# Power_Ctrl_Board_SCH.net
KiCad netlist of a schematic drawn in Altium Designer
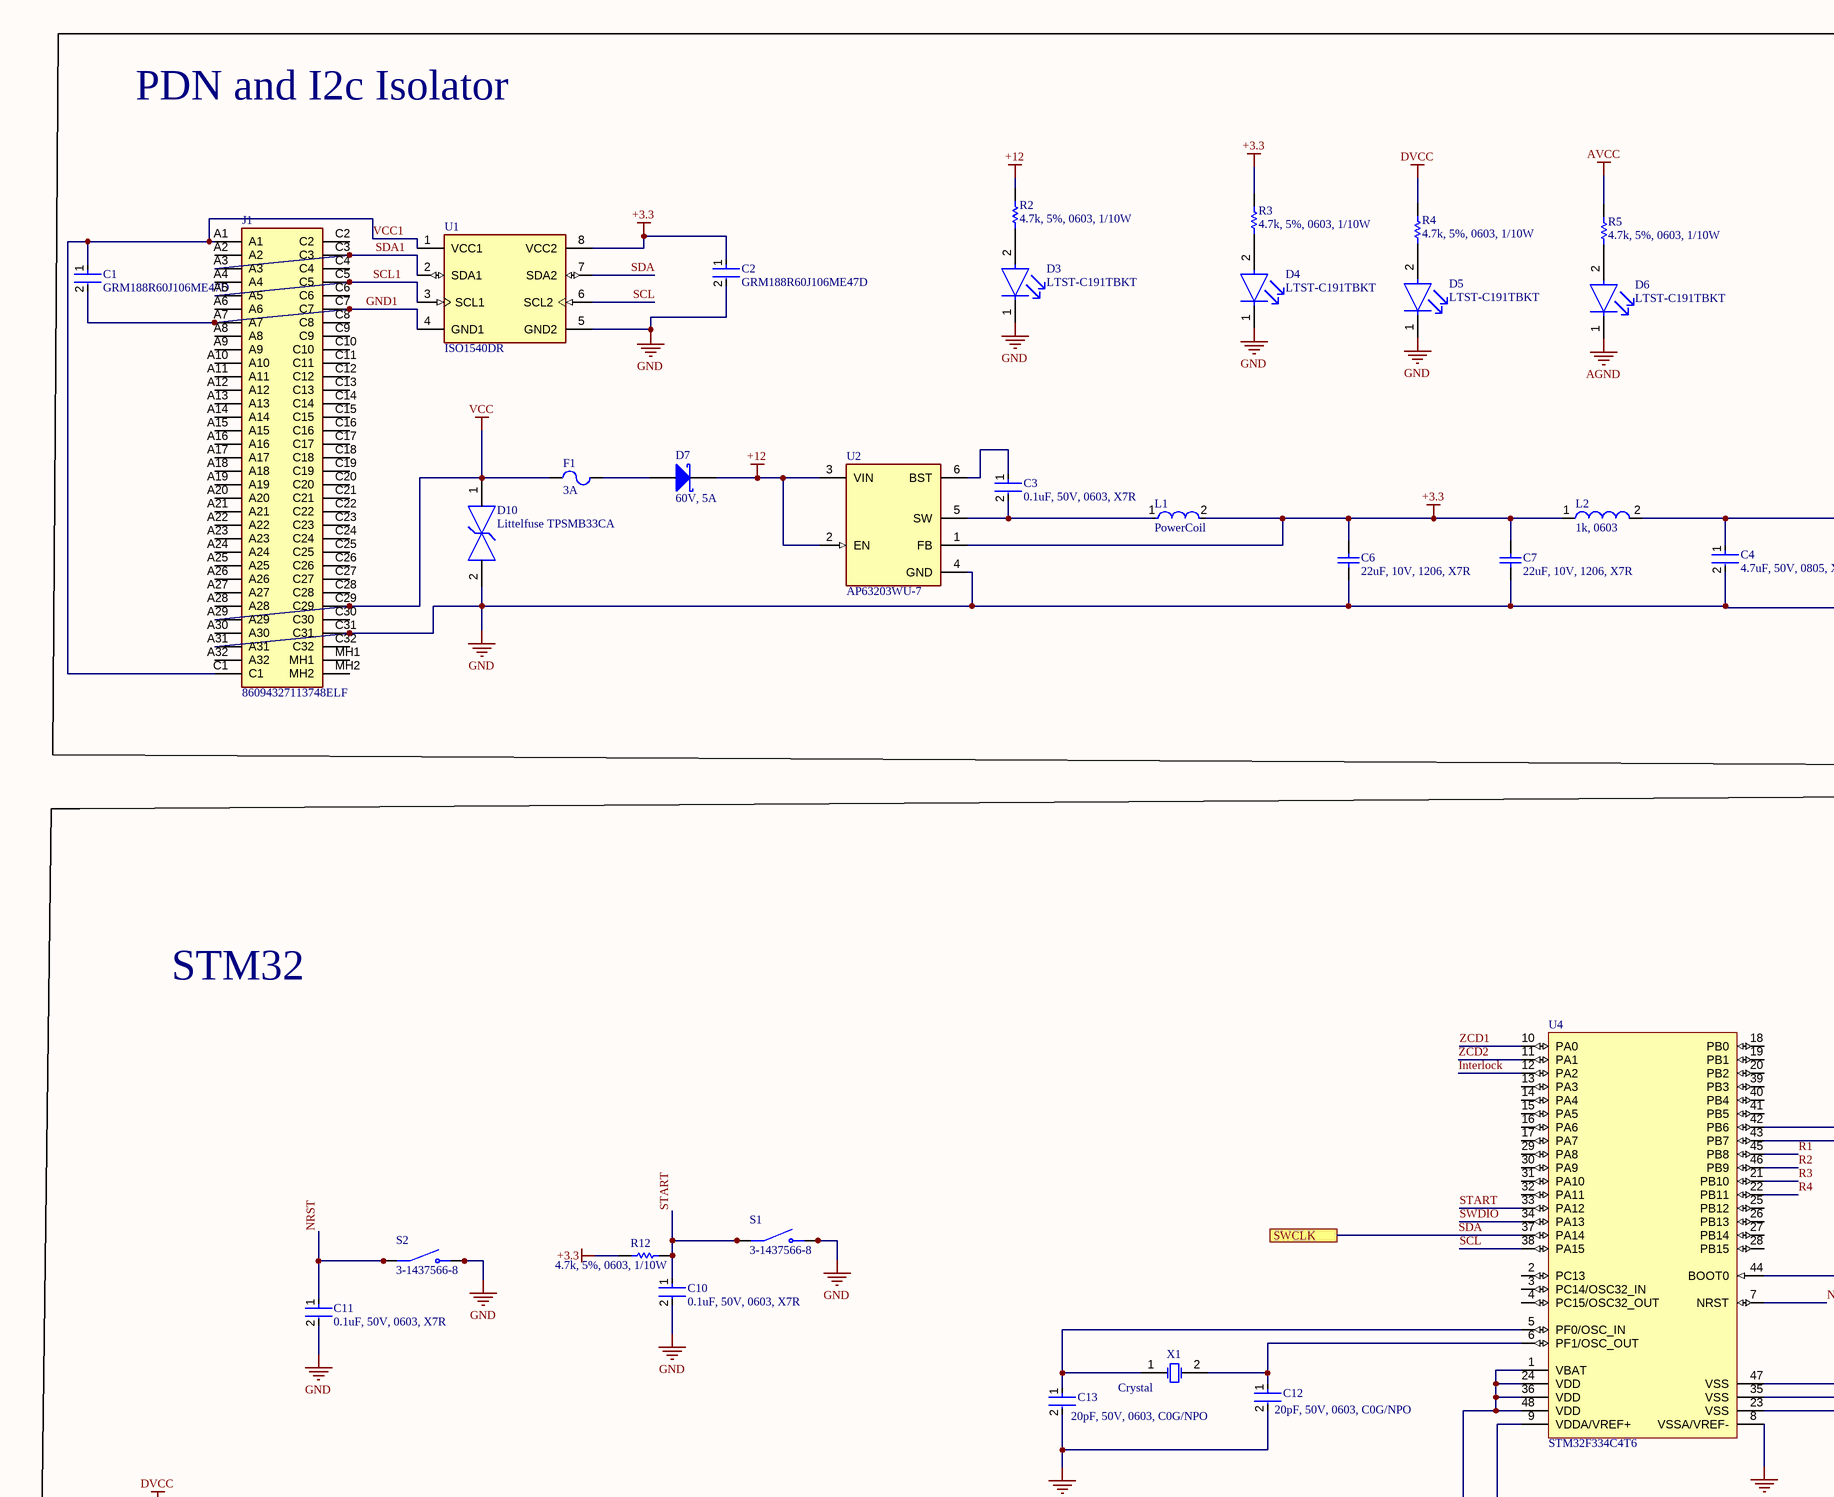
[diagram p0: Power_Ctrl_Board_SCH.SchDoc, top left]
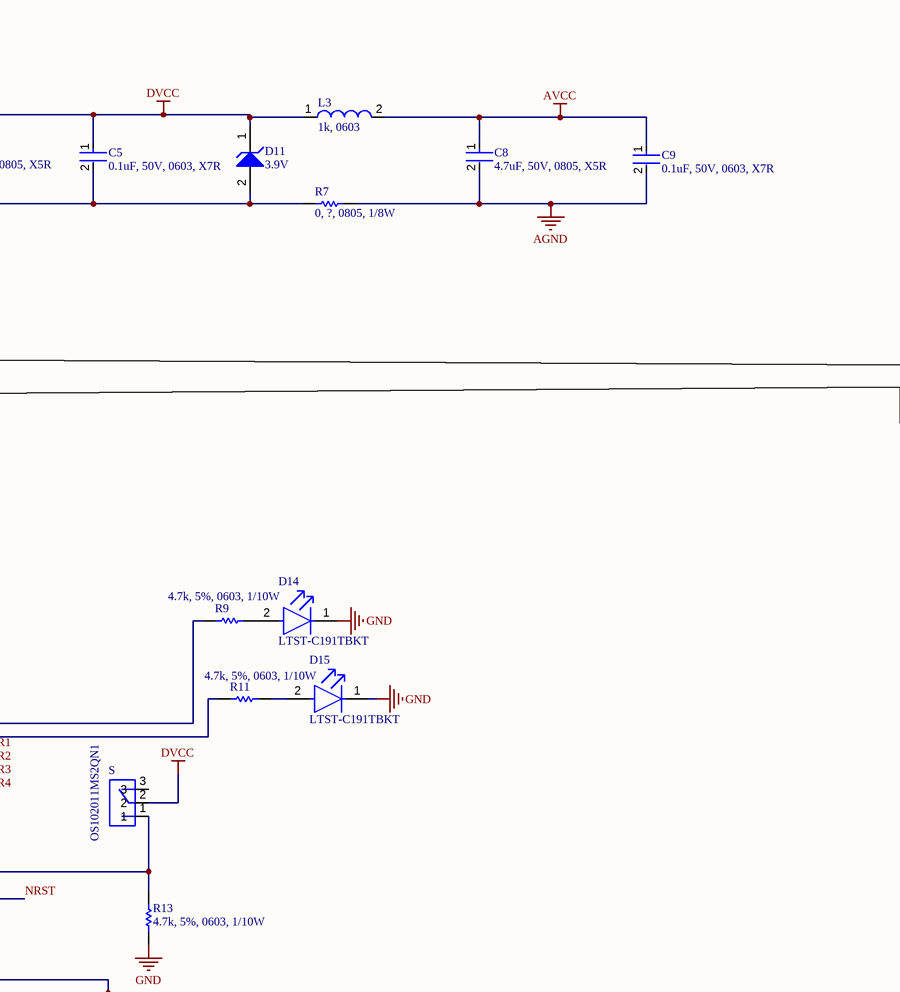
[diagram p1: Power_Ctrl_Board_SCH.SchDoc, top middle]
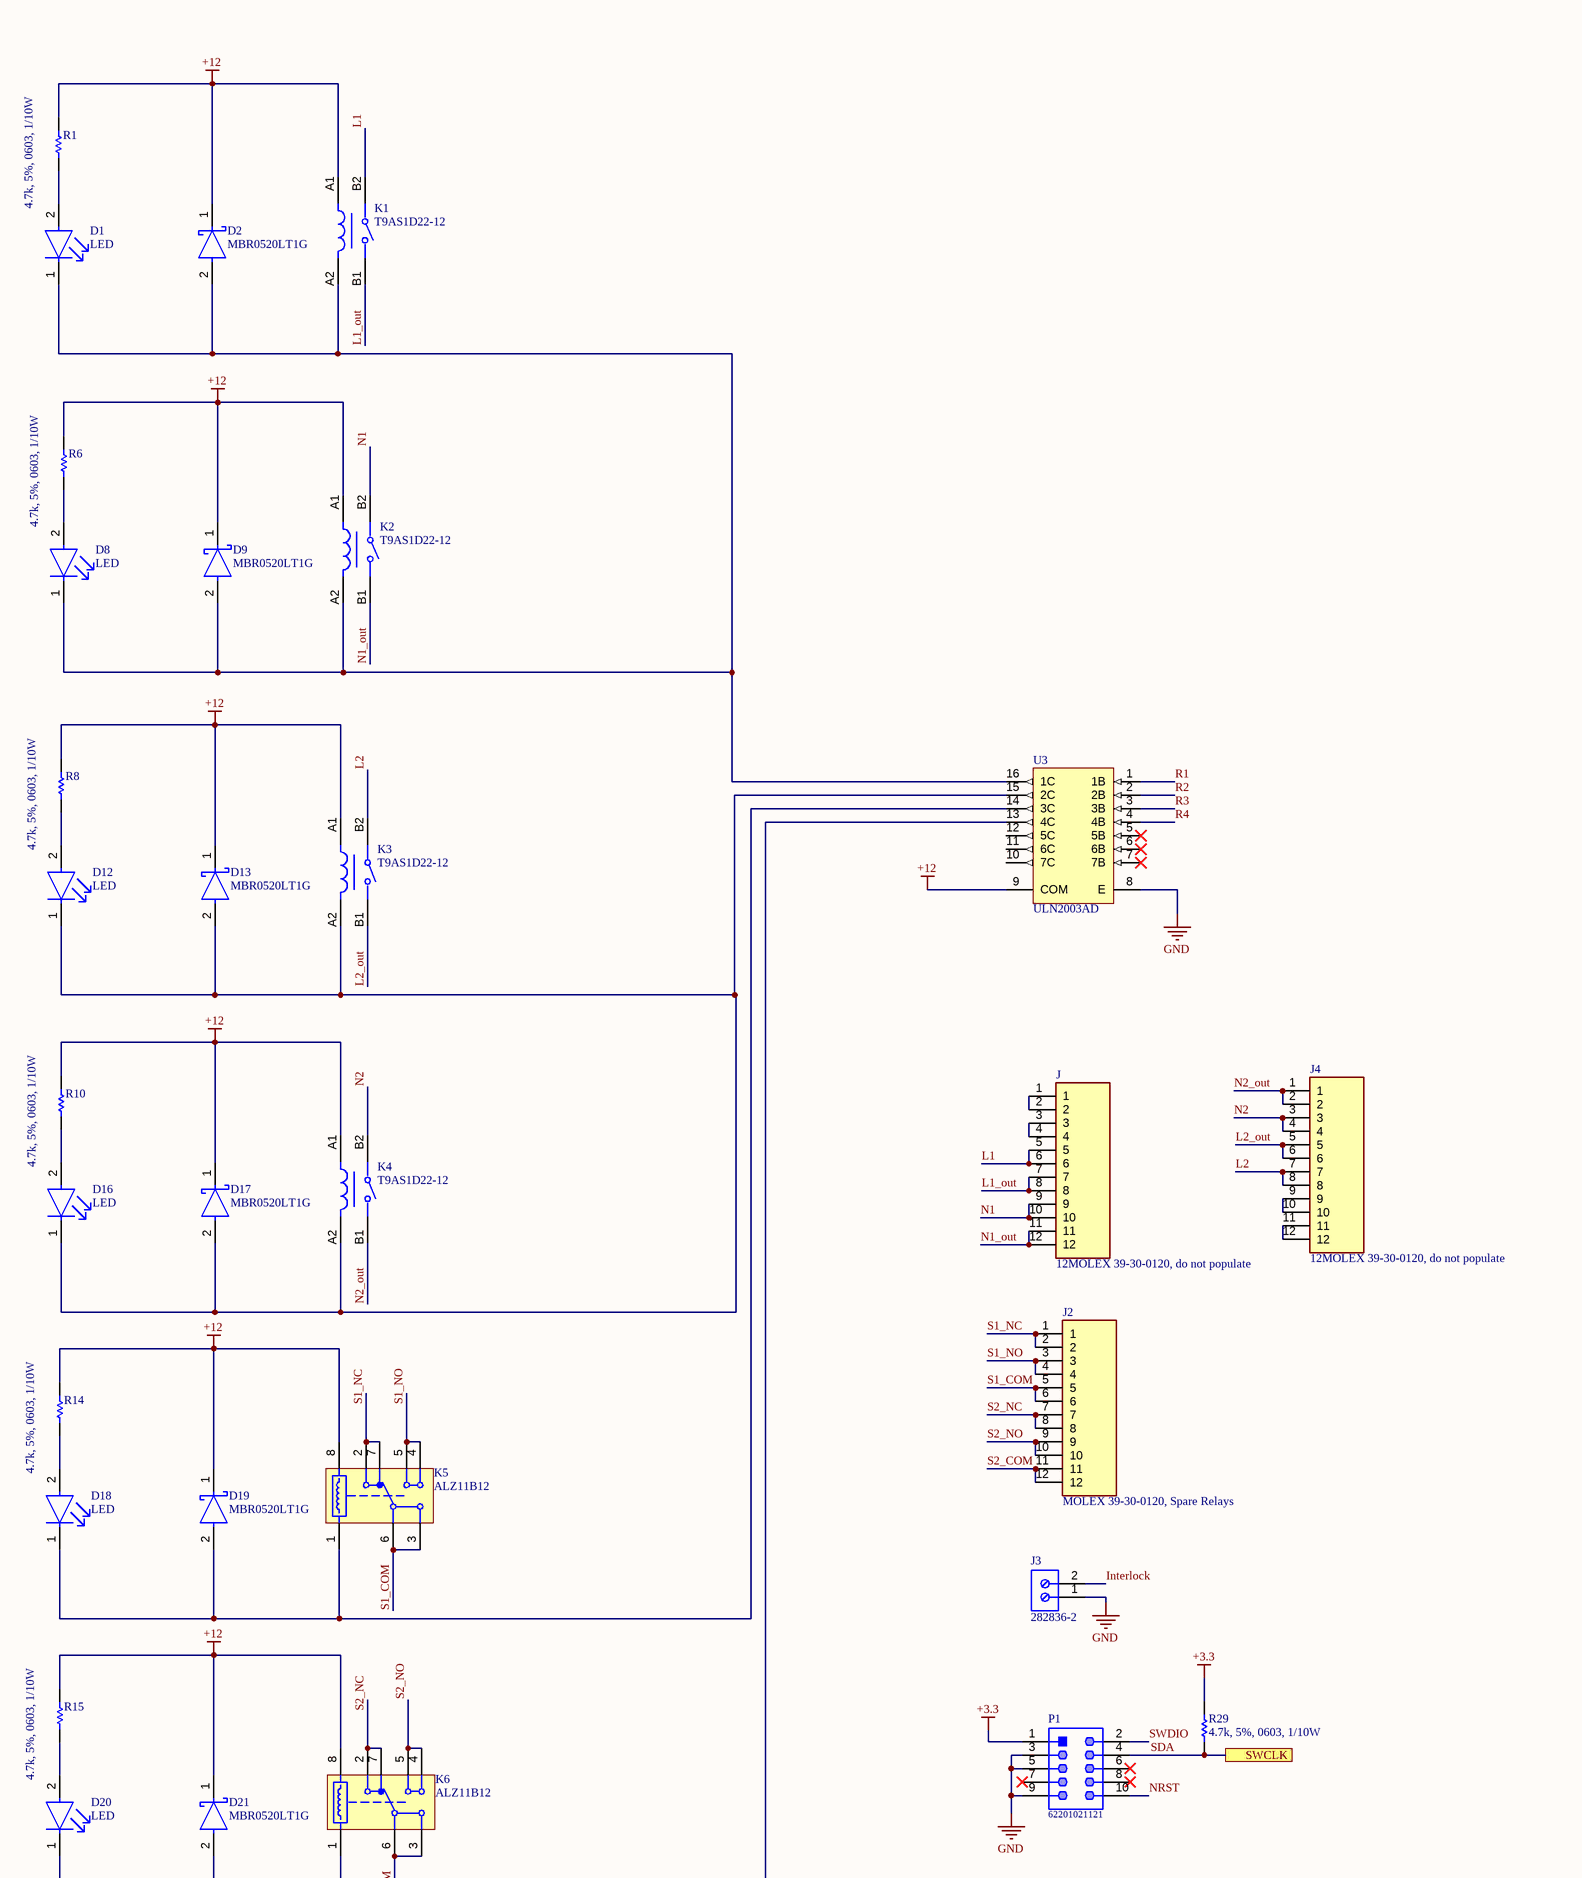
[diagram p2: Power_Ctrl_Board_SCH.SchDoc, top right]
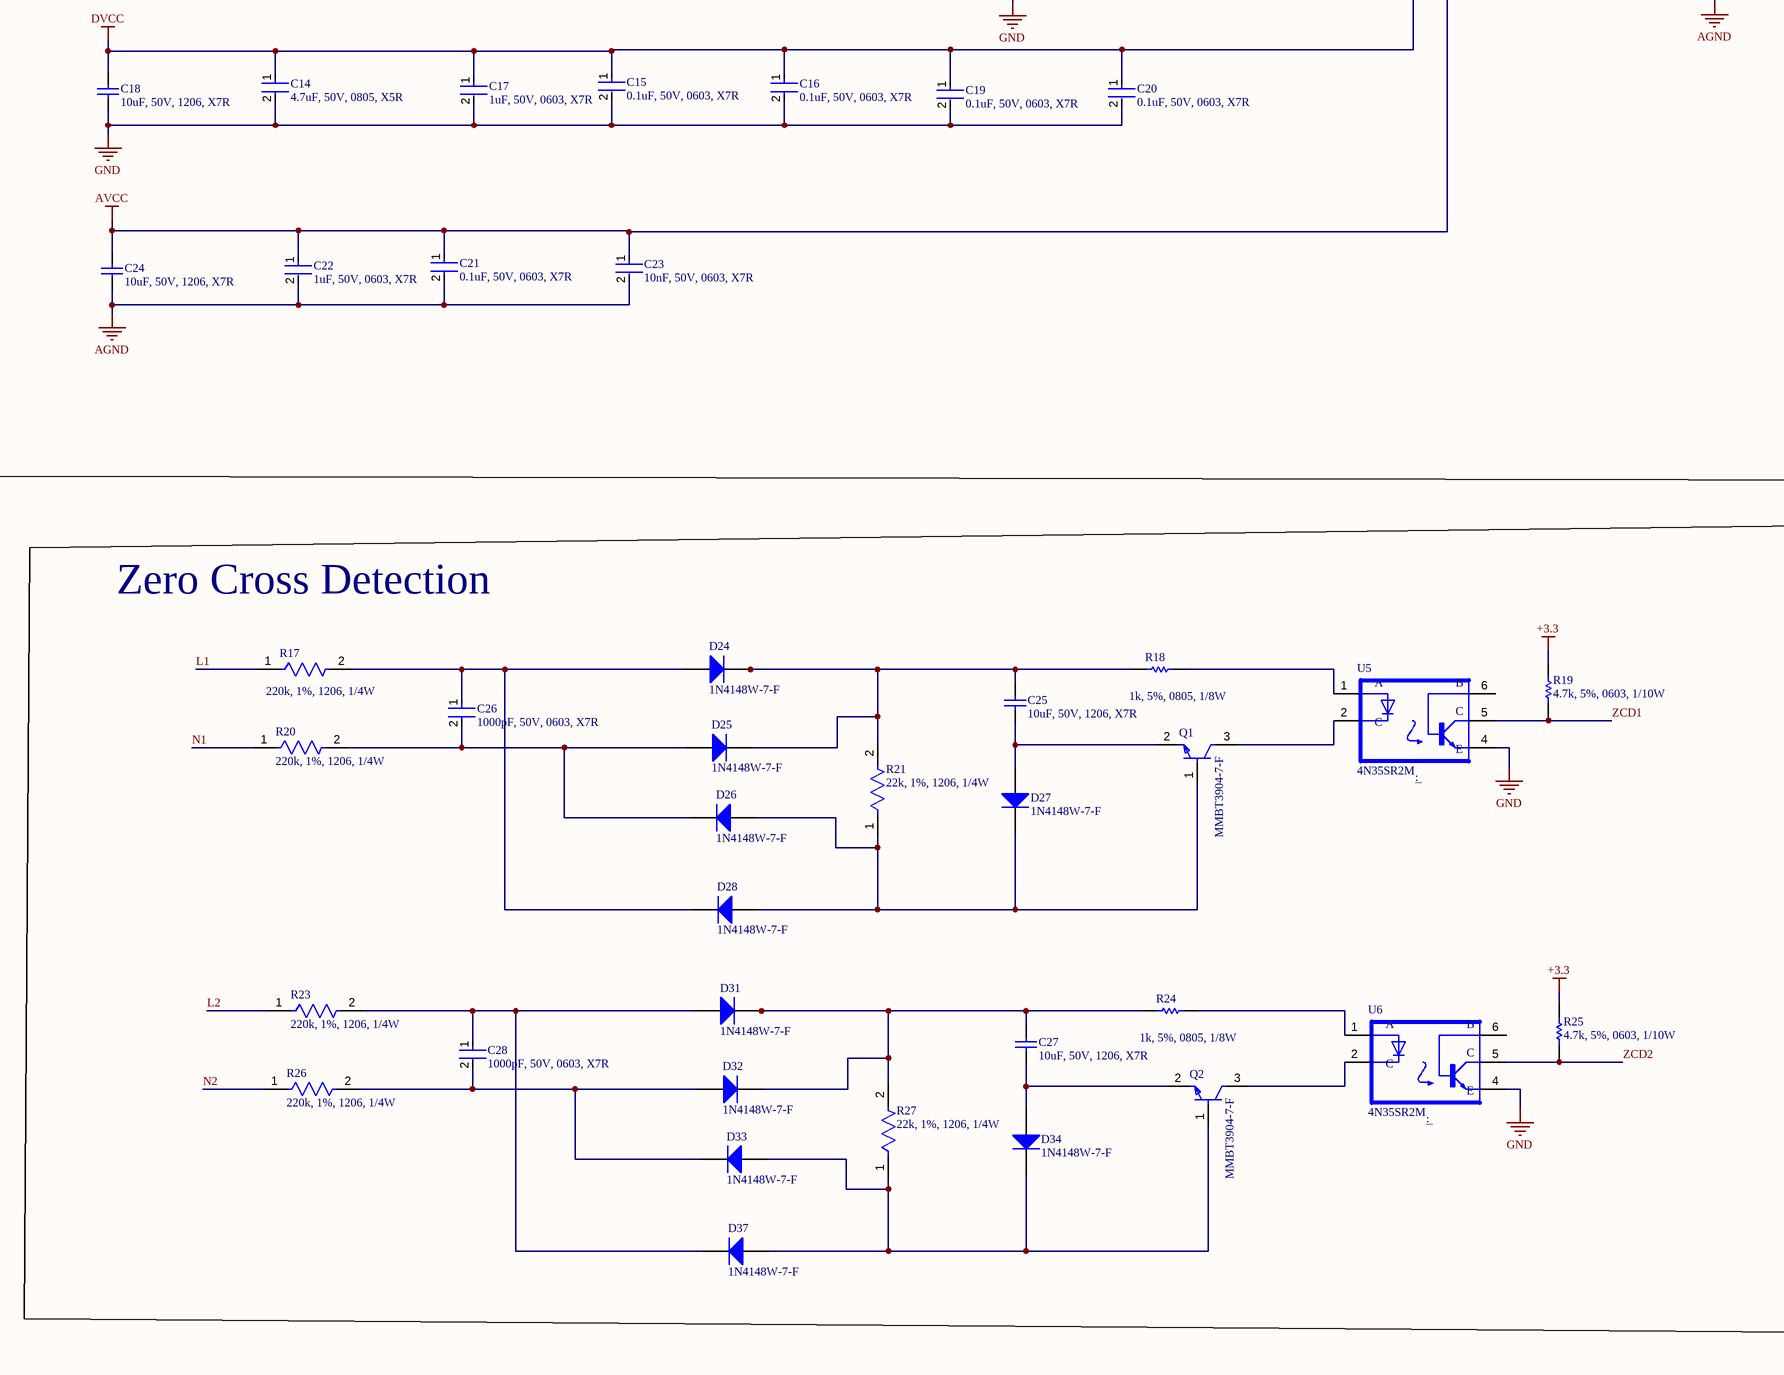
[diagram p3: Power_Ctrl_Board_SCH.SchDoc, bottom left]
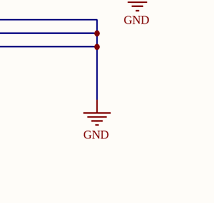
[diagram p4: Power_Ctrl_Board_SCH.SchDoc, bottom middle]
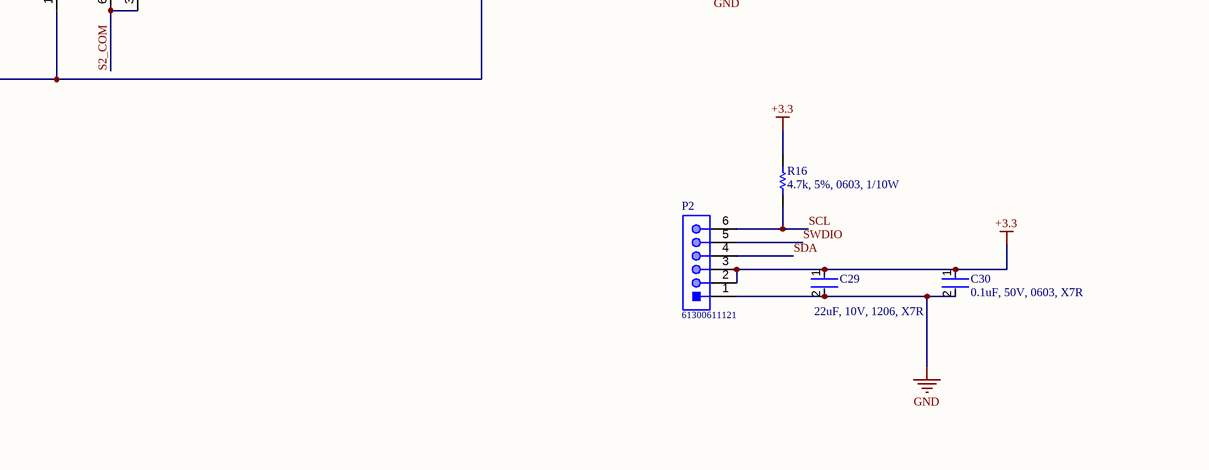
[diagram p5: Power_Ctrl_Board_SCH.SchDoc, bottom right]

(export (version "E")
  (design (tool "Eeschema 10.0.6"))
  (components
    (comp (ref "C1")
      (value "GRM188R60J106ME47D")
      (footprint "FP-GRM188-0_1-e0_2_0_55-IPC_A")
      (description "Chip Multilayer Ceramic Capacitors for General Purpose, 0603, 10uF, X5R, 15%, 20%, 6.3V")
      (fields (field (name "VOLTAGE") "6.3V") (field (name "TOLERANCE") "20%"))
      (libsource (lib "Altium Content Vault") (part "02cd4be3c70576c341d710602a673aa"))
    )
    (comp (ref "C2")
      (value "GRM188R60J106ME47D")
      (footprint "FP-GRM188-0_1-e0_2_0_55-IPC_A")
      (description "Chip Multilayer Ceramic Capacitors for General Purpose, 0603, 10uF, X5R, 15%, 20%, 6.3V")
      (fields (field (name "VOLTAGE") "6.3V") (field (name "TOLERANCE") "20%"))
      (libsource (lib "Altium Content Vault") (part "02cd4be3c70576c341d710602a673aa"))
    )
    (comp (ref "C3")
      (value "0.1uF, 50V, 0603, X7R")
      (footprint "FP-GRM188-0_1-e0_2_0_55-IPC_A")
      (description "Chip Multilayer Ceramic Capacitors for General Purpose, 0603, 10uF, X5R, 15%, 20%, 6.3V")
      (fields (field (name "VOLTAGE") "6.3V") (field (name "TOLERANCE") "20%"))
      (libsource (lib "Altium Content Vault") (part "02cd4be3c70576c341d710602a673aa"))
    )
    (comp (ref "C4")
      (value "4.7uF, 50V, 0805, X5R")
      (footprint "FP-C0805C-DG-MFG")
      (description "CAP CER 10UF 10V X5R 0805")
      (fields (field (name "TOLERANCE") "10%") (field (name "MANUFACTURER PART NUMBER") "C0805C106K8PACTU"))
      (libsource (lib "Altium Content Vault") (part "11868f565c42a9108669ba33697ecf6"))
    )
    (comp (ref "C5")
      (value "0.1uF, 50V, 0603, X7R")
      (footprint "FP-GRM188-0_1-e0_2_0_55-IPC_A")
      (description "Chip Multilayer Ceramic Capacitors for General Purpose, 0603, 10uF, X5R, 15%, 20%, 6.3V")
      (fields (field (name "VOLTAGE") "6.3V") (field (name "TOLERANCE") "20%"))
      (libsource (lib "Altium Content Vault") (part "02cd4be3c70576c341d710602a673aa"))
    )
    (comp (ref "C6")
      (value "22uF, 10V, 1206, X7R")
      (footprint "AVX-1206-2_L")
      (description "Chip Capacitor, 1 nF, +/- 10%, -55 to 125 degC, 1206 (3216 Metric), RoHS, Tape and Reel")
      (fields (field (name "TOLERANCE") "10%") (field (name "PARTNUMBER") "1206GC102KAT1A"))
      (libsource (lib "Altium Content Vault") (part "CAP-NP-2"))
    )
    (comp (ref "C7")
      (value "22uF, 10V, 1206, X7R")
      (footprint "AVX-1206-2_L")
      (description "Chip Capacitor, 1 nF, +/- 10%, -55 to 125 degC, 1206 (3216 Metric), RoHS, Tape and Reel")
      (fields (field (name "TOLERANCE") "10%") (field (name "PARTNUMBER") "1206GC102KAT1A"))
      (libsource (lib "Altium Content Vault") (part "CAP-NP-2"))
    )
    (comp (ref "C8")
      (value "4.7uF, 50V, 0805, X5R")
      (footprint "FP-C0805C-DG-MFG")
      (description "CAP CER 10UF 10V X5R 0805")
      (fields (field (name "TOLERANCE") "10%") (field (name "MANUFACTURER PART NUMBER") "C0805C106K8PACTU"))
      (libsource (lib "Altium Content Vault") (part "11868f565c42a9108669ba33697ecf6"))
    )
    (comp (ref "C9")
      (value "0.1uF, 50V, 0603, X7R")
      (footprint "FP-GRM188-0_1-e0_2_0_55-IPC_A")
      (description "Chip Multilayer Ceramic Capacitors for General Purpose, 0603, 10uF, X5R, 15%, 20%, 6.3V")
      (fields (field (name "VOLTAGE") "6.3V") (field (name "TOLERANCE") "20%"))
      (libsource (lib "Altium Content Vault") (part "02cd4be3c70576c341d710602a673aa"))
    )
    (comp (ref "C10")
      (value "0.1uF, 50V, 0603, X7R")
      (footprint "FP-GRM188-0_1-e0_2_0_55-IPC_A")
      (description "Chip Multilayer Ceramic Capacitors for General Purpose, 0603, 10uF, X5R, 15%, 20%, 6.3V")
      (fields (field (name "VOLTAGE") "6.3V") (field (name "TOLERANCE") "20%"))
      (libsource (lib "Altium Content Vault") (part "02cd4be3c70576c341d710602a673aa"))
    )
    (comp (ref "C11")
      (value "0.1uF, 50V, 0603, X7R")
      (footprint "FP-GRM188-0_1-e0_2_0_55-IPC_A")
      (description "Chip Multilayer Ceramic Capacitors for General Purpose, 0603, 10uF, X5R, 15%, 20%, 6.3V")
      (fields (field (name "VOLTAGE") "6.3V") (field (name "TOLERANCE") "20%"))
      (libsource (lib "Altium Content Vault") (part "02cd4be3c70576c341d710602a673aa"))
    )
    (comp (ref "C12")
      (value "20pF, 50V, 0603, C0G/NPO")
      (footprint "FP-GRM188-0_1-e0_2_0_55-IPC_A")
      (description "Chip Multilayer Ceramic Capacitors for General Purpose, 0603, 10uF, X5R, 15%, 20%, 6.3V")
      (fields (field (name "VOLTAGE") "6.3V") (field (name "TOLERANCE") "20%"))
      (libsource (lib "Altium Content Vault") (part "02cd4be3c70576c341d710602a673aa"))
    )
    (comp (ref "C13")
      (value "20pF, 50V, 0603, C0G/NPO")
      (footprint "FP-GRM188-0_1-e0_2_0_55-IPC_A")
      (description "Chip Multilayer Ceramic Capacitors for General Purpose, 0603, 10uF, X5R, 15%, 20%, 6.3V")
      (fields (field (name "VOLTAGE") "6.3V") (field (name "TOLERANCE") "20%"))
      (libsource (lib "Altium Content Vault") (part "02cd4be3c70576c341d710602a673aa"))
    )
    (comp (ref "C14")
      (value "4.7uF, 50V, 0805, X5R")
      (footprint "FP-C0805C-DG-MFG")
      (description "CAP CER 10UF 10V X5R 0805")
      (fields (field (name "TOLERANCE") "10%") (field (name "MANUFACTURER PART NUMBER") "C0805C106K8PACTU"))
      (libsource (lib "Altium Content Vault") (part "11868f565c42a9108669ba33697ecf6"))
    )
    (comp (ref "C15")
      (value "0.1uF, 50V, 0603, X7R")
      (footprint "FP-GRM188-0_1-e0_2_0_55-IPC_A")
      (description "Chip Multilayer Ceramic Capacitors for General Purpose, 0603, 10uF, X5R, 15%, 20%, 6.3V")
      (fields (field (name "VOLTAGE") "6.3V") (field (name "TOLERANCE") "20%"))
      (libsource (lib "Altium Content Vault") (part "02cd4be3c70576c341d710602a673aa"))
    )
    (comp (ref "C16")
      (value "0.1uF, 50V, 0603, X7R")
      (footprint "FP-GRM188-0_1-e0_2_0_55-IPC_A")
      (description "Chip Multilayer Ceramic Capacitors for General Purpose, 0603, 10uF, X5R, 15%, 20%, 6.3V")
      (fields (field (name "VOLTAGE") "6.3V") (field (name "TOLERANCE") "20%"))
      (libsource (lib "Altium Content Vault") (part "02cd4be3c70576c341d710602a673aa"))
    )
    (comp (ref "C17")
      (value "1uF, 50V, 0603, X7R")
      (footprint "FP-GRM188-0_1-e0_2_0_55-IPC_A")
      (description "Chip Multilayer Ceramic Capacitors for General Purpose, 0603, 10uF, X5R, 15%, 20%, 6.3V")
      (fields (field (name "VOLTAGE") "6.3V") (field (name "TOLERANCE") "20%"))
      (libsource (lib "Altium Content Vault") (part "02cd4be3c70576c341d710602a673aa"))
    )
    (comp (ref "C18")
      (value "10uF, 50V, 1206, X7R")
      (footprint "AVX-1206-2_L")
      (description "Chip Capacitor, 1 nF, +/- 10%, -55 to 125 degC, 1206 (3216 Metric), RoHS, Tape and Reel")
      (fields (field (name "TOLERANCE") "10%") (field (name "PARTNUMBER") "1206GC102KAT1A"))
      (libsource (lib "Altium Content Vault") (part "CAP-NP-2"))
    )
    (comp (ref "C19")
      (value "0.1uF, 50V, 0603, X7R")
      (footprint "FP-GRM188-0_1-e0_2_0_55-IPC_A")
      (description "Chip Multilayer Ceramic Capacitors for General Purpose, 0603, 10uF, X5R, 15%, 20%, 6.3V")
      (fields (field (name "VOLTAGE") "6.3V") (field (name "TOLERANCE") "20%"))
      (libsource (lib "Altium Content Vault") (part "02cd4be3c70576c341d710602a673aa"))
    )
    (comp (ref "C20")
      (value "0.1uF, 50V, 0603, X7R")
      (footprint "FP-GRM188-0_1-e0_2_0_55-IPC_A")
      (description "Chip Multilayer Ceramic Capacitors for General Purpose, 0603, 10uF, X5R, 15%, 20%, 6.3V")
      (fields (field (name "VOLTAGE") "6.3V") (field (name "TOLERANCE") "20%"))
      (libsource (lib "Altium Content Vault") (part "02cd4be3c70576c341d710602a673aa"))
    )
    (comp (ref "C21")
      (value "0.1uF, 50V, 0603, X7R")
      (footprint "FP-GRM188-0_1-e0_2_0_55-IPC_A")
      (description "Chip Multilayer Ceramic Capacitors for General Purpose, 0603, 10uF, X5R, 15%, 20%, 6.3V")
      (fields (field (name "VOLTAGE") "6.3V") (field (name "TOLERANCE") "20%"))
      (libsource (lib "Altium Content Vault") (part "02cd4be3c70576c341d710602a673aa"))
    )
    (comp (ref "C22")
      (value "1uF, 50V, 0603, X7R")
      (footprint "FP-GRM188-0_1-e0_2_0_55-IPC_A")
      (description "Chip Multilayer Ceramic Capacitors for General Purpose, 0603, 10uF, X5R, 15%, 20%, 6.3V")
      (fields (field (name "VOLTAGE") "6.3V") (field (name "TOLERANCE") "20%"))
      (libsource (lib "Altium Content Vault") (part "02cd4be3c70576c341d710602a673aa"))
    )
    (comp (ref "C23")
      (value "10nF, 50V, 0603, X7R")
      (footprint "FP-GRM188-0_1-e0_2_0_55-IPC_A")
      (description "Chip Multilayer Ceramic Capacitors for General Purpose, 0603, 10uF, X5R, 15%, 20%, 6.3V")
      (fields (field (name "VOLTAGE") "6.3V") (field (name "TOLERANCE") "20%"))
      (libsource (lib "Altium Content Vault") (part "02cd4be3c70576c341d710602a673aa"))
    )
    (comp (ref "C24")
      (value "10uF, 50V, 1206, X7R")
      (footprint "AVX-1206-2_L")
      (description "Chip Capacitor, 1 nF, +/- 10%, -55 to 125 degC, 1206 (3216 Metric), RoHS, Tape and Reel")
      (fields (field (name "TOLERANCE") "10%") (field (name "PARTNUMBER") "1206GC102KAT1A"))
      (libsource (lib "Altium Content Vault") (part "CAP-NP-2"))
    )
    (comp (ref "C25")
      (value "10uF, 50V, 1206, X7R")
      (footprint "AVX-1206-2_L")
      (description "Chip Capacitor, 1 nF, +/- 10%, -55 to 125 degC, 1206 (3216 Metric), RoHS, Tape and Reel")
      (fields (field (name "TOLERANCE") "10%") (field (name "PARTNUMBER") "1206GC102KAT1A"))
      (libsource (lib "Altium Content Vault") (part "CAP-NP-2"))
    )
    (comp (ref "C26")
      (value "1000pF, 50V, 0603, X7R")
      (footprint "FP-GRM188-0_1-e0_2_0_55-IPC_A")
      (description "Chip Multilayer Ceramic Capacitors for General Purpose, 0603, 10uF, X5R, 15%, 20%, 6.3V")
      (fields (field (name "VOLTAGE") "6.3V") (field (name "TOLERANCE") "20%"))
      (libsource (lib "Altium Content Vault") (part "02cd4be3c70576c341d710602a673aa"))
    )
    (comp (ref "C27")
      (value "10uF, 50V, 1206, X7R")
      (footprint "AVX-1206-2_L")
      (description "Chip Capacitor, 1 nF, +/- 10%, -55 to 125 degC, 1206 (3216 Metric), RoHS, Tape and Reel")
      (fields (field (name "TOLERANCE") "10%") (field (name "PARTNUMBER") "1206GC102KAT1A"))
      (libsource (lib "Altium Content Vault") (part "CAP-NP-2"))
    )
    (comp (ref "C28")
      (value "1000pF, 50V, 0603, X7R")
      (footprint "FP-GRM188-0_1-e0_2_0_55-IPC_A")
      (description "Chip Multilayer Ceramic Capacitors for General Purpose, 0603, 10uF, X5R, 15%, 20%, 6.3V")
      (fields (field (name "VOLTAGE") "6.3V") (field (name "TOLERANCE") "20%"))
      (libsource (lib "Altium Content Vault") (part "02cd4be3c70576c341d710602a673aa"))
    )
    (comp (ref "C29")
      (value "22uF, 10V, 1206, X7R")
      (footprint "FP-GRM188-0_1-e0_2_0_55-IPC_A")
      (description "Chip Multilayer Ceramic Capacitors for General Purpose, 0603, 10uF, X5R, 15%, 20%, 6.3V")
      (fields (field (name "VOLTAGE") "6.3V") (field (name "TOLERANCE") "20%"))
      (libsource (lib "Altium Content Vault") (part "02cd4be3c70576c341d710602a673aa"))
    )
    (comp (ref "C30")
      (value "0.1uF, 50V, 0603, X7R")
      (footprint "FP-GRM188-0_1-e0_2_0_55-IPC_A")
      (description "Chip Multilayer Ceramic Capacitors for General Purpose, 0603, 10uF, X5R, 15%, 20%, 6.3V")
      (fields (field (name "VOLTAGE") "6.3V") (field (name "TOLERANCE") "20%"))
      (libsource (lib "Altium Content Vault") (part "02cd4be3c70576c341d710602a673aa"))
    )
    (comp (ref "D1")
      (value "LED")
      (footprint "FP-LTST-C191TBKT-MFG")
      (description "LED BLUE CLEAR CHIP SMD")
      (libsource (lib "Altium Content Vault") (part "8706943c75ba83719d021d2fdc84c58"))
    )
    (comp (ref "D2")
      (value "MBR0520LT1G")
      (footprint "FP-425-04-IPC_C")
      (description "DIODE SCHOTTKY 20V 500MA SOD123")
      (libsource (lib "Altium Content Vault") (part "1d6ec82d83fb6aee721767c19dac4b9"))
    )
    (comp (ref "D3")
      (value "LTST-C191TBKT")
      (footprint "FP-LTST-C191TBKT-MFG")
      (description "LED BLUE CLEAR CHIP SMD")
      (libsource (lib "Altium Content Vault") (part "8706943c75ba83719d021d2fdc84c58"))
    )
    (comp (ref "D4")
      (value "LTST-C191TBKT")
      (footprint "FP-LTST-C191TBKT-MFG")
      (description "LED BLUE CLEAR CHIP SMD")
      (libsource (lib "Altium Content Vault") (part "8706943c75ba83719d021d2fdc84c58"))
    )
    (comp (ref "D5")
      (value "LTST-C191TBKT")
      (footprint "FP-LTST-C191TBKT-MFG")
      (description "LED BLUE CLEAR CHIP SMD")
      (libsource (lib "Altium Content Vault") (part "8706943c75ba83719d021d2fdc84c58"))
    )
    (comp (ref "D6")
      (value "LTST-C191TBKT")
      (footprint "FP-LTST-C191TBKT-MFG")
      (description "LED BLUE CLEAR CHIP SMD")
      (libsource (lib "Altium Content Vault") (part "8706943c75ba83719d021d2fdc84c58"))
    )
    (comp (ref "D7")
      (value "60V, 5A")
      (footprint "NXP-SOD128_V")
      (description "Schottky Barrier Rectifier, 3 A, 30 V, -55 to 150 degC, 2-Pin SOD128, RoHS, Tape and Reel")
      (fields (field (name "MANUFACTURER") "NXP Semiconductors"))
      (libsource (lib "Altium Content Vault") (part "DSKY-AK-2"))
    )
    (comp (ref "D8")
      (value "LED")
      (footprint "FP-LTST-C191TBKT-MFG")
      (description "LED BLUE CLEAR CHIP SMD")
      (libsource (lib "Altium Content Vault") (part "8706943c75ba83719d021d2fdc84c58"))
    )
    (comp (ref "D9")
      (value "MBR0520LT1G")
      (footprint "FP-425-04-IPC_C")
      (description "DIODE SCHOTTKY 20V 500MA SOD123")
      (libsource (lib "Altium Content Vault") (part "1d6ec82d83fb6aee721767c19dac4b9"))
    )
    (comp (ref "D10")
      (value "Littelfuse TPSMB33CA")
      (footprint "FP-SMAJ-CA-MFG")
      (description "TVS DIODE 12V 19.9V DO214AC")
      (fields
        (field (name "MANUFACTURER PART NUMBER") "SMAJ12CA")
        (field (name "OCTOPART") "https://octopart.com/smaj12ca-littelfuse-349824")
      )
      (libsource (lib "Altium Content Vault") (part "876f4347bf90aa6f500f43e3cd03972"))
    )
    (comp (ref "D11")
      (value "3.9V")
      (footprint "ONSC-SOD-123-2-425-04_V")
      (description "Zener Voltage Regulator, 500 mW, 2-Pin SOD-123, Pb-Free, Tape and Reel")
      (fields (field (name "PARTNUMBER") "MMSZ18T1G") (field (name "MANUFACTURER") "On Semiconductor"))
      (libsource (lib "Altium Content Vault") (part "ONSC-K1A2-2"))
    )
    (comp (ref "D12")
      (value "LED")
      (footprint "FP-LTST-C191TBKT-MFG")
      (description "LED BLUE CLEAR CHIP SMD")
      (libsource (lib "Altium Content Vault") (part "8706943c75ba83719d021d2fdc84c58"))
    )
    (comp (ref "D13")
      (value "MBR0520LT1G")
      (footprint "FP-425-04-IPC_C")
      (description "DIODE SCHOTTKY 20V 500MA SOD123")
      (libsource (lib "Altium Content Vault") (part "1d6ec82d83fb6aee721767c19dac4b9"))
    )
    (comp (ref "D14")
      (value "LTST-C191TBKT")
      (footprint "FP-LTST-C191TBKT-MFG")
      (description "LED BLUE CLEAR CHIP SMD")
      (libsource (lib "Altium Content Vault") (part "8706943c75ba83719d021d2fdc84c58"))
    )
    (comp (ref "D15")
      (value "LTST-C191TBKT")
      (footprint "FP-LTST-C191TBKT-MFG")
      (description "LED BLUE CLEAR CHIP SMD")
      (libsource (lib "Altium Content Vault") (part "8706943c75ba83719d021d2fdc84c58"))
    )
    (comp (ref "D16")
      (value "LED")
      (footprint "FP-LTST-C191TBKT-MFG")
      (description "LED BLUE CLEAR CHIP SMD")
      (libsource (lib "Altium Content Vault") (part "8706943c75ba83719d021d2fdc84c58"))
    )
    (comp (ref "D17")
      (value "MBR0520LT1G")
      (footprint "FP-425-04-IPC_C")
      (description "DIODE SCHOTTKY 20V 500MA SOD123")
      (libsource (lib "Altium Content Vault") (part "1d6ec82d83fb6aee721767c19dac4b9"))
    )
    (comp (ref "D18")
      (value "LED")
      (footprint "FP-LTST-C191TBKT-MFG")
      (description "LED BLUE CLEAR CHIP SMD")
      (libsource (lib "Altium Content Vault") (part "8706943c75ba83719d021d2fdc84c58"))
    )
    (comp (ref "D19")
      (value "MBR0520LT1G")
      (footprint "FP-425-04-IPC_C")
      (description "DIODE SCHOTTKY 20V 500MA SOD123")
      (libsource (lib "Altium Content Vault") (part "1d6ec82d83fb6aee721767c19dac4b9"))
    )
    (comp (ref "D20")
      (value "LED")
      (footprint "FP-LTST-C191TBKT-MFG")
      (description "LED BLUE CLEAR CHIP SMD")
      (libsource (lib "Altium Content Vault") (part "8706943c75ba83719d021d2fdc84c58"))
    )
    (comp (ref "D21")
      (value "MBR0520LT1G")
      (footprint "FP-425-04-IPC_C")
      (description "DIODE SCHOTTKY 20V 500MA SOD123")
      (libsource (lib "Altium Content Vault") (part "1d6ec82d83fb6aee721767c19dac4b9"))
    )
    (comp (ref "D24")
      (value "1N4148W-7-F")
      (footprint "DIOD-SOD123-2_V")
      (description "Fast Switching Diode, 100 V, 0.15 A, -65 to 150 degC, 2-Pin?SOD123, RoHS, Tape and Reel")
      (fields (field (name "MANUFACTURER") "DiodesIncorporated"))
      (libsource (lib "Altium Content Vault") (part "D-AK-2"))
    )
    (comp (ref "D25")
      (value "1N4148W-7-F")
      (footprint "DIOD-SOD123-2_V")
      (description "Fast Switching Diode, 100 V, 0.15 A, -65 to 150 degC, 2-Pin?SOD123, RoHS, Tape and Reel")
      (fields (field (name "MANUFACTURER") "DiodesIncorporated"))
      (libsource (lib "Altium Content Vault") (part "D-AK-2"))
    )
    (comp (ref "D26")
      (value "1N4148W-7-F")
      (footprint "DIOD-SOD123-2_V")
      (description "Fast Switching Diode, 100 V, 0.15 A, -65 to 150 degC, 2-Pin?SOD123, RoHS, Tape and Reel")
      (fields (field (name "MANUFACTURER") "DiodesIncorporated"))
      (libsource (lib "Altium Content Vault") (part "D-AK-2"))
    )
    (comp (ref "D27")
      (value "1N4148W-7-F")
      (footprint "DIOD-SOD123-2_V")
      (description "Fast Switching Diode, 100 V, 0.15 A, -65 to 150 degC, 2-Pin?SOD123, RoHS, Tape and Reel")
      (fields (field (name "MANUFACTURER") "DiodesIncorporated"))
      (libsource (lib "Altium Content Vault") (part "D-AK-2"))
    )
    (comp (ref "D28")
      (value "1N4148W-7-F")
      (footprint "DIOD-SOD123-2_V")
      (description "Fast Switching Diode, 100 V, 0.15 A, -65 to 150 degC, 2-Pin?SOD123, RoHS, Tape and Reel")
      (fields (field (name "MANUFACTURER") "DiodesIncorporated"))
      (libsource (lib "Altium Content Vault") (part "D-AK-2"))
    )
    (comp (ref "D31")
      (value "1N4148W-7-F")
      (footprint "DIOD-SOD123-2_V")
      (description "Fast Switching Diode, 100 V, 0.15 A, -65 to 150 degC, 2-Pin?SOD123, RoHS, Tape and Reel")
      (fields (field (name "MANUFACTURER") "DiodesIncorporated"))
      (libsource (lib "Altium Content Vault") (part "D-AK-2"))
    )
    (comp (ref "D32")
      (value "1N4148W-7-F")
      (footprint "DIOD-SOD123-2_V")
      (description "Fast Switching Diode, 100 V, 0.15 A, -65 to 150 degC, 2-Pin?SOD123, RoHS, Tape and Reel")
      (fields (field (name "MANUFACTURER") "DiodesIncorporated"))
      (libsource (lib "Altium Content Vault") (part "D-AK-2"))
    )
    (comp (ref "D33")
      (value "1N4148W-7-F")
      (footprint "DIOD-SOD123-2_V")
      (description "Fast Switching Diode, 100 V, 0.15 A, -65 to 150 degC, 2-Pin?SOD123, RoHS, Tape and Reel")
      (fields (field (name "MANUFACTURER") "DiodesIncorporated"))
      (libsource (lib "Altium Content Vault") (part "D-AK-2"))
    )
    (comp (ref "D34")
      (value "1N4148W-7-F")
      (footprint "DIOD-SOD123-2_V")
      (description "Fast Switching Diode, 100 V, 0.15 A, -65 to 150 degC, 2-Pin?SOD123, RoHS, Tape and Reel")
      (fields (field (name "MANUFACTURER") "DiodesIncorporated"))
      (libsource (lib "Altium Content Vault") (part "D-AK-2"))
    )
    (comp (ref "D37")
      (value "1N4148W-7-F")
      (footprint "DIOD-SOD123-2_V")
      (description "Fast Switching Diode, 100 V, 0.15 A, -65 to 150 degC, 2-Pin?SOD123, RoHS, Tape and Reel")
      (fields (field (name "MANUFACTURER") "DiodesIncorporated"))
      (libsource (lib "Altium Content Vault") (part "D-AK-2"))
    )
    (comp (ref "F1")
      (value "3A")
      (footprint "LFUS-45X_V")
      (description "Fuse, 125 V, 500 mA, -55 to 125 degC, 2-Pin SMD, RoHS, Tape and Reel")
      (fields (field (name "MANUFACTURER") "Littelfuse"))
      (libsource (lib "Altium Content Vault") (part "FUSE-2"))
    )
    (comp (ref "J")
      (value "12MOLEX 39-30-0120, do not populate")
      (footprint "TE_1-1586038-2")
      (description "Conn Power HDR 12 POS 4.2mm Solder ST Thru-Hole 12 Terminal 1 Port Tray")
      (fields (field (name "MP") "1-1586038-2") (field (name "MF") "TE Connectivity"))
      (libsource (lib "1-1586038-2") (part "1-1586038-2"))
    )
    (comp (ref "J1")
      (value "86094327113748ELF")
      (footprint "SamacSys:86094327113748ELF")
      (description "Connector")
      (fields (field (name "MOUSER PART NUMBER") "649-869432713748ELF"))
      (libsource (lib "SamacSys") (part "86094327113748ELF"))
    )
    (comp (ref "J2")
      (value "MOLEX 39-30-0120, Spare Relays")
      (footprint "TE_1-1586038-2")
      (description "Conn Power HDR 12 POS 4.2mm Solder ST Thru-Hole 12 Terminal 1 Port Tray")
      (fields (field (name "MP") "1-1586038-2") (field (name "MF") "TE Connectivity"))
      (libsource (lib "1-1586038-2") (part "1-1586038-2"))
    )
    (comp (ref "J3")
      (value "282836-2")
      (footprint "TECO-282836-2_V")
      (description "Female Header, Pitch 5 mm, 1 x 2 Position, Height 10 mm, Tail Length 3.5 mm, Rohs, Bulk")
      (fields (field (name "VOLTAGE") "300V") (field (name "MANUFACTURER") "TE Connectivity"))
      (libsource (lib "Altium Content Vault") (part "CN-1P-F-TB2"))
    )
    (comp (ref "J4")
      (value "12MOLEX 39-30-0120, do not populate")
      (footprint "TE_1-1586038-2")
      (description "Conn Power HDR 12 POS 4.2mm Solder ST Thru-Hole 12 Terminal 1 Port Tray")
      (fields (field (name "MP") "1-1586038-2") (field (name "MF") "TE Connectivity"))
      (libsource (lib "1-1586038-2") (part "1-1586038-2"))
    )
    (comp (ref "K1")
      (value "T9AS1D22-12")
      (footprint "FP-T9AS1D22-12-MFG")
      (description "RELAY GEN PURPOSE SPST 30A 12V")
      (fields
        (field (name "OCTOPART") "https://octopart.com/t9as1d22-12-te+connectivity-46521723")
        (field (name "MANUFACTURER") "TE Connectivity")
      )
      (libsource (lib "Altium Content Vault") (part "8e293d1f856185b239982dffafedd3a"))
    )
    (comp (ref "K2")
      (value "T9AS1D22-12")
      (footprint "FP-T9AS1D22-12-MFG")
      (description "RELAY GEN PURPOSE SPST 30A 12V")
      (fields
        (field (name "OCTOPART") "https://octopart.com/t9as1d22-12-te+connectivity-46521723")
        (field (name "MANUFACTURER") "TE Connectivity")
      )
      (libsource (lib "Altium Content Vault") (part "8e293d1f856185b239982dffafedd3a"))
    )
    (comp (ref "K3")
      (value "T9AS1D22-12")
      (footprint "FP-T9AS1D22-12-MFG")
      (description "RELAY GEN PURPOSE SPST 30A 12V")
      (fields
        (field (name "OCTOPART") "https://octopart.com/t9as1d22-12-te+connectivity-46521723")
        (field (name "MANUFACTURER") "TE Connectivity")
      )
      (libsource (lib "Altium Content Vault") (part "8e293d1f856185b239982dffafedd3a"))
    )
    (comp (ref "K4")
      (value "T9AS1D22-12")
      (footprint "FP-T9AS1D22-12-MFG")
      (description "RELAY GEN PURPOSE SPST 30A 12V")
      (fields
        (field (name "OCTOPART") "https://octopart.com/t9as1d22-12-te+connectivity-46521723")
        (field (name "MANUFACTURER") "TE Connectivity")
      )
      (libsource (lib "Altium Content Vault") (part "8e293d1f856185b239982dffafedd3a"))
    )
    (comp (ref "K5")
      (value "ALZ11B12")
      (footprint "PNSC-LZ-8-2880x1250x1570_V")
      (fields (field (name "MANUFACTURER") "Panasonic"))
      (libsource (lib "Altium Content Vault") (part "PNSC-ALZ11B12-LZ-8-2880x1250x1570-8"))
    )
    (comp (ref "K6")
      (value "ALZ11B12")
      (footprint "PNSC-LZ-8-2880x1250x1570_V")
      (fields (field (name "MANUFACTURER") "Panasonic"))
      (libsource (lib "Altium Content Vault") (part "PNSC-ALZ11B12-LZ-8-2880x1250x1570-8"))
    )
    (comp (ref "L1")
      (value "PowerCoil")
      (footprint "FP-NRS5030-H_3_0-MFG")
      (description "FIXED IND 15UH 1.4A 125 MOHM SMD")
      (fields (field (name "TOLERANCE") "20%"))
      (libsource (lib "Altium Content Vault") (part "725321dda6339637d4d059423bc1c3c"))
    )
    (comp (ref "L2")
      (value "1k, 0603")
      (footprint "SMD-0603")
      (description "SMD EMI Suppression Ferrite Bead WE-CBF, Z = 30 Ohm")
      (libsource (lib "Altium Content Vault") (part "PAS-IND-INDUCTOR-2"))
    )
    (comp (ref "L3")
      (value "1k, 0603")
      (footprint "SMD-0603")
      (description "SMD EMI Suppression Ferrite Bead WE-CBF, Z = 30 Ohm")
      (libsource (lib "Altium Content Vault") (part "PAS-IND-INDUCTOR-2"))
    )
    (comp (ref "P1")
      (value "62201021121")
      (footprint "62201021121")
      (description "THT Vertical Pin Header WR-PHD, Pitch 1.27 mm, Dual Row, 10 pins")
      (fields (field (name "MANUFACTURER") "Wurth Elektronik") (field (name "PUBLISHER") "WurthElektronik"))
      (libsource (lib "Altium Content Vault") (part "WE-CN-2P-M-R10"))
    )
    (comp (ref "P2")
      (value "61300611121")
      (footprint "61300611121")
      (description "THT Vertical Pin Header WR-PHD, Pitch 2.54 mm, Single Row, 6 pins")
      (fields (field (name "MANUFACTURER") "Wurth Elektronik") (field (name "PUBLISHER") "WurthElektronik"))
      (libsource (lib "Altium Content Vault") (part "WE-CN-1P-M-R6"))
    )
    (comp (ref "Q1")
      (value "MMBT3904-7-F")
      (footprint "FP-SOT23-IPC_A")
      (description "TRANS NPN 40V 0.2A SMD SOT23-3")
      (libsource (lib "Altium Content Vault") (part "b44e953556f554d0102664c7d152cb4"))
    )
    (comp (ref "Q2")
      (value "MMBT3904-7-F")
      (footprint "FP-SOT23-IPC_A")
      (description "TRANS NPN 40V 0.2A SMD SOT23-3")
      (libsource (lib "Altium Content Vault") (part "b44e953556f554d0102664c7d152cb4"))
    )
    (comp (ref "R1")
      (value "4.7k, 5%, 0603, 1/10W")
      (footprint "RESC1609X55X30LL15T15")
      (description "Chip Resistor, 10 KOhm, +/- 1%, 0.1 W, -55 to 155 degC, 0603 (1608 Metric), RoHS, Tape and Reel")
      (fields (field (name "TOLERANCE") "1%") (field (name "MANUFACTURER") "Panasonic"))
      (libsource (lib "Altium Content Vault") (part "RES-2"))
    )
    (comp (ref "R2")
      (value "4.7k, 5%, 0603, 1/10W")
      (footprint "RESC1609X55X30LL15T15")
      (description "Chip Resistor, 10 KOhm, +/- 1%, 0.1 W, -55 to 155 degC, 0603 (1608 Metric), RoHS, Tape and Reel")
      (fields (field (name "TOLERANCE") "1%") (field (name "MANUFACTURER") "Panasonic"))
      (libsource (lib "Altium Content Vault") (part "RES-2"))
    )
    (comp (ref "R3")
      (value "4.7k, 5%, 0603, 1/10W")
      (footprint "RESC1609X55X30LL15T15")
      (description "Chip Resistor, 10 KOhm, +/- 1%, 0.1 W, -55 to 155 degC, 0603 (1608 Metric), RoHS, Tape and Reel")
      (fields (field (name "TOLERANCE") "1%") (field (name "MANUFACTURER") "Panasonic"))
      (libsource (lib "Altium Content Vault") (part "RES-2"))
    )
    (comp (ref "R4")
      (value "4.7k, 5%, 0603, 1/10W")
      (footprint "RESC1609X55X30LL15T15")
      (description "Chip Resistor, 10 KOhm, +/- 1%, 0.1 W, -55 to 155 degC, 0603 (1608 Metric), RoHS, Tape and Reel")
      (fields (field (name "TOLERANCE") "1%") (field (name "MANUFACTURER") "Panasonic"))
      (libsource (lib "Altium Content Vault") (part "RES-2"))
    )
    (comp (ref "R5")
      (value "4.7k, 5%, 0603, 1/10W")
      (footprint "RESC1609X55X30LL15T15")
      (description "Chip Resistor, 10 KOhm, +/- 1%, 0.1 W, -55 to 155 degC, 0603 (1608 Metric), RoHS, Tape and Reel")
      (fields (field (name "TOLERANCE") "1%") (field (name "MANUFACTURER") "Panasonic"))
      (libsource (lib "Altium Content Vault") (part "RES-2"))
    )
    (comp (ref "R6")
      (value "4.7k, 5%, 0603, 1/10W")
      (footprint "RESC1609X55X30LL15T15")
      (description "Chip Resistor, 10 KOhm, +/- 1%, 0.1 W, -55 to 155 degC, 0603 (1608 Metric), RoHS, Tape and Reel")
      (fields (field (name "TOLERANCE") "1%") (field (name "MANUFACTURER") "Panasonic"))
      (libsource (lib "Altium Content Vault") (part "RES-2"))
    )
    (comp (ref "R7")
      (value "0, ?, 0805, 1/8W")
      (footprint "RESC2013X50X30LL20T20")
      (fields (field (name "MANUFACTURER") "Vishay Dale") (field (name "PART NUMBER") "CRCW08050000Z0EA"))
      (libsource (lib "Altium Content Vault") (part "RES"))
    )
    (comp (ref "R8")
      (value "4.7k, 5%, 0603, 1/10W")
      (footprint "RESC1609X55X30LL15T15")
      (description "Chip Resistor, 10 KOhm, +/- 1%, 0.1 W, -55 to 155 degC, 0603 (1608 Metric), RoHS, Tape and Reel")
      (fields (field (name "TOLERANCE") "1%") (field (name "MANUFACTURER") "Panasonic"))
      (libsource (lib "Altium Content Vault") (part "RES-2"))
    )
    (comp (ref "R9")
      (value "4.7k, 5%, 0603, 1/10W")
      (footprint "RESC1609X55X30LL15T15")
      (description "Chip Resistor, 10 KOhm, +/- 1%, 0.1 W, -55 to 155 degC, 0603 (1608 Metric), RoHS, Tape and Reel")
      (fields (field (name "TOLERANCE") "1%") (field (name "MANUFACTURER") "Panasonic"))
      (libsource (lib "Altium Content Vault") (part "RES-2"))
    )
    (comp (ref "R10")
      (value "4.7k, 5%, 0603, 1/10W")
      (footprint "RESC1609X55X30LL15T15")
      (description "Chip Resistor, 10 KOhm, +/- 1%, 0.1 W, -55 to 155 degC, 0603 (1608 Metric), RoHS, Tape and Reel")
      (fields (field (name "TOLERANCE") "1%") (field (name "MANUFACTURER") "Panasonic"))
      (libsource (lib "Altium Content Vault") (part "RES-2"))
    )
    (comp (ref "R11")
      (value "4.7k, 5%, 0603, 1/10W")
      (footprint "RESC1609X55X30LL15T15")
      (description "Chip Resistor, 10 KOhm, +/- 1%, 0.1 W, -55 to 155 degC, 0603 (1608 Metric), RoHS, Tape and Reel")
      (fields (field (name "TOLERANCE") "1%") (field (name "MANUFACTURER") "Panasonic"))
      (libsource (lib "Altium Content Vault") (part "RES-2"))
    )
    (comp (ref "R12")
      (value "4.7k, 5%, 0603, 1/10W")
      (footprint "RESC1609X55X30LL15T15")
      (description "Chip Resistor, 10 KOhm, +/- 1%, 0.1 W, -55 to 155 degC, 0603 (1608 Metric), RoHS, Tape and Reel")
      (fields (field (name "TOLERANCE") "1%") (field (name "MANUFACTURER") "Panasonic"))
      (libsource (lib "Altium Content Vault") (part "RES-2"))
    )
    (comp (ref "R13")
      (value "4.7k, 5%, 0603, 1/10W")
      (footprint "RESC1609X55X30LL15T15")
      (description "Chip Resistor, 10 KOhm, +/- 1%, 0.1 W, -55 to 155 degC, 0603 (1608 Metric), RoHS, Tape and Reel")
      (fields (field (name "TOLERANCE") "1%") (field (name "MANUFACTURER") "Panasonic"))
      (libsource (lib "Altium Content Vault") (part "RES-2"))
    )
    (comp (ref "R14")
      (value "4.7k, 5%, 0603, 1/10W")
      (footprint "RESC1609X55X30LL15T15")
      (description "Chip Resistor, 10 KOhm, +/- 1%, 0.1 W, -55 to 155 degC, 0603 (1608 Metric), RoHS, Tape and Reel")
      (fields (field (name "TOLERANCE") "1%") (field (name "MANUFACTURER") "Panasonic"))
      (libsource (lib "Altium Content Vault") (part "RES-2"))
    )
    (comp (ref "R15")
      (value "4.7k, 5%, 0603, 1/10W")
      (footprint "RESC1609X55X30LL15T15")
      (description "Chip Resistor, 10 KOhm, +/- 1%, 0.1 W, -55 to 155 degC, 0603 (1608 Metric), RoHS, Tape and Reel")
      (fields (field (name "TOLERANCE") "1%") (field (name "MANUFACTURER") "Panasonic"))
      (libsource (lib "Altium Content Vault") (part "RES-2"))
    )
    (comp (ref "R16")
      (value "4.7k, 5%, 0603, 1/10W")
      (footprint "RESC1609X55X30LL15T15")
      (description "Chip Resistor, 10 KOhm, +/- 1%, 0.1 W, -55 to 155 degC, 0603 (1608 Metric), RoHS, Tape and Reel")
      (fields (field (name "TOLERANCE") "1%") (field (name "MANUFACTURER") "Panasonic"))
      (libsource (lib "Altium Content Vault") (part "RES-2"))
    )
    (comp (ref "R17")
      (value "220k, 1%, 1206, 1/4W")
      (footprint "FP-RC1206-MFG")
      (description "RES SMD 0 OHM JUMPER 1/4W 1206")
      (fields
        (field (name "MANUFACTURER PART NUMBER") "RC1206JR-070RL")
        (field (name "MANUFACTURER") "YAGEO")
      )
      (libsource (lib "Altium Content Vault") (part "1029c3af85768c4190bb7ad29bc67b5"))
    )
    (comp (ref "R18")
      (value "1k, 5%, 0805, 1/8W")
      (footprint "RESC2013X50X30LL20T20")
      (fields (field (name "MANUFACTURER") "Vishay Dale") (field (name "PART NUMBER") "CRCW08050000Z0EA"))
      (libsource (lib "Altium Content Vault") (part "RES"))
    )
    (comp (ref "R19")
      (value "4.7k, 5%, 0603, 1/10W")
      (footprint "RESC1609X55X30LL15T15")
      (description "Chip Resistor, 10 KOhm, +/- 1%, 0.1 W, -55 to 155 degC, 0603 (1608 Metric), RoHS, Tape and Reel")
      (fields (field (name "TOLERANCE") "1%") (field (name "MANUFACTURER") "Panasonic"))
      (libsource (lib "Altium Content Vault") (part "RES-2"))
    )
    (comp (ref "R20")
      (value "220k, 1%, 1206, 1/4W")
      (footprint "FP-RC1206-MFG")
      (description "RES SMD 0 OHM JUMPER 1/4W 1206")
      (fields
        (field (name "MANUFACTURER PART NUMBER") "RC1206JR-070RL")
        (field (name "MANUFACTURER") "YAGEO")
      )
      (libsource (lib "Altium Content Vault") (part "1029c3af85768c4190bb7ad29bc67b5"))
    )
    (comp (ref "R21")
      (value "22k, 1%, 1206, 1/4W")
      (footprint "FP-RC1206-MFG")
      (description "RES SMD 0 OHM JUMPER 1/4W 1206")
      (fields
        (field (name "MANUFACTURER PART NUMBER") "RC1206JR-070RL")
        (field (name "MANUFACTURER") "YAGEO")
      )
      (libsource (lib "Altium Content Vault") (part "1029c3af85768c4190bb7ad29bc67b5"))
    )
    (comp (ref "R23")
      (value "220k, 1%, 1206, 1/4W")
      (footprint "FP-RC1206-MFG")
      (description "RES SMD 0 OHM JUMPER 1/4W 1206")
      (fields
        (field (name "MANUFACTURER PART NUMBER") "RC1206JR-070RL")
        (field (name "MANUFACTURER") "YAGEO")
      )
      (libsource (lib "Altium Content Vault") (part "1029c3af85768c4190bb7ad29bc67b5"))
    )
    (comp (ref "R24")
      (value "1k, 5%, 0805, 1/8W")
      (footprint "RESC2013X50X30LL20T20")
      (fields (field (name "MANUFACTURER") "Vishay Dale") (field (name "PART NUMBER") "CRCW08050000Z0EA"))
      (libsource (lib "Altium Content Vault") (part "RES"))
    )
    (comp (ref "R25")
      (value "4.7k, 5%, 0603, 1/10W")
      (footprint "RESC1609X55X30LL15T15")
      (description "Chip Resistor, 10 KOhm, +/- 1%, 0.1 W, -55 to 155 degC, 0603 (1608 Metric), RoHS, Tape and Reel")
      (fields (field (name "TOLERANCE") "1%") (field (name "MANUFACTURER") "Panasonic"))
      (libsource (lib "Altium Content Vault") (part "RES-2"))
    )
    (comp (ref "R26")
      (value "220k, 1%, 1206, 1/4W")
      (footprint "FP-RC1206-MFG")
      (description "RES SMD 0 OHM JUMPER 1/4W 1206")
      (fields
        (field (name "MANUFACTURER PART NUMBER") "RC1206JR-070RL")
        (field (name "MANUFACTURER") "YAGEO")
      )
      (libsource (lib "Altium Content Vault") (part "1029c3af85768c4190bb7ad29bc67b5"))
    )
    (comp (ref "R27")
      (value "22k, 1%, 1206, 1/4W")
      (footprint "FP-RC1206-MFG")
      (description "RES SMD 0 OHM JUMPER 1/4W 1206")
      (fields
        (field (name "MANUFACTURER PART NUMBER") "RC1206JR-070RL")
        (field (name "MANUFACTURER") "YAGEO")
      )
      (libsource (lib "Altium Content Vault") (part "1029c3af85768c4190bb7ad29bc67b5"))
    )
    (comp (ref "R29")
      (value "4.7k, 5%, 0603, 1/10W")
      (footprint "RESC1609X55X30LL15T15")
      (description "Chip Resistor, 10 KOhm, +/- 1%, 0.1 W, -55 to 155 degC, 0603 (1608 Metric), RoHS, Tape and Reel")
      (fields (field (name "TOLERANCE") "1%") (field (name "MANUFACTURER") "Panasonic"))
      (libsource (lib "Altium Content Vault") (part "RES-2"))
    )
    (comp (ref "S")
      (value "OS102011MS2QN1")
      (footprint "SW_OS102011MS2QN1")
      (description "Slide Switch SPDT Through Hole")
      (fields (field (name "MF") "C&K"))
      (libsource (lib "OS102011MS2QN1") (part "OS102011MS2QN1"))
    )
    (comp (ref "S1")
      (value "3-1437566-8")
      (footprint "SW_3-1437566-8")
      (description "Switch Tactile OFF (ON) SPST Round Button Gull Wing 0.05A 12VDC 1VA 1.57N SMD Loose Piece")
      (fields (field (name "MF") "TE Connectivity / AMP"))
      (libsource (lib "3-1437566-8") (part "3-1437566-8"))
    )
    (comp (ref "S2")
      (value "3-1437566-8")
      (footprint "SW_3-1437566-8")
      (description "Switch Tactile OFF (ON) SPST Round Button Gull Wing 0.05A 12VDC 1VA 1.57N SMD Loose Piece")
      (fields (field (name "MF") "TE Connectivity / AMP"))
      (libsource (lib "3-1437566-8") (part "3-1437566-8"))
    )
    (comp (ref "U1")
      (value "ISO1540DR")
      (footprint "FP-D0008A-MFG")
      (description "DGTL ISO 2.5KV 2CH I2C 8SOIC")
      (fields
        (field (name "OCTOPART") "https://octopart.com/iso1540dr-texas+instruments-24334113")
        (field (name "MANUFACTURER") "Texas Instruments")
      )
      (libsource (lib "Altium Content Vault") (part "d824faccee5d143ad01692c0ddd1d85"))
    )
    (comp (ref "U2")
      (value "AP63203WU-7")
      (footprint "FP-TSOT26-MFG")
      (description "IC REG BUCK 3.3V 2A TSOT26")
      (fields
        (field (name "MANUFACTURER") "Diodes Inc.")
        (field (name "OCTOPART") "https://octopart.com/ap63203wu-7-diodes+inc.-98099550")
      )
      (libsource (lib "Altium Content Vault") (part "0e61c2974d7114b43f01ef96ae2e524"))
    )
    (comp (ref "U3")
      (value "ULN2003AD")
      (footprint "D0016A_M")
      (fields (field (name "MANUFACTURER") "TexasInstruments"))
      (libsource (lib "Altium Content Vault") (part "TI-ULX200X-D-16"))
    )
    (comp (ref "U4")
      (value "STM32F334C4T6")
      (footprint "STM-LQFP48_M")
      (libsource (lib "Altium Content Vault") (part "MC-ARM-STM32F334-LQFP48"))
    )
    (comp (ref "U5")
      (value "4N35SR2M")
      (footprint "OPTO_4N35SM")
      (description "Transistor Output Optocouplers PHOTO TRANS")
      (fields (field (name "MF") "ON Semiconductor / Fairchild") (field (name "MP") "4N35SM"))
      (libsource (lib "4N35SM") (part "4N35SM"))
    )
    (comp (ref "U6")
      (value "4N35SR2M")
      (footprint "OPTO_4N35SM")
      (description "Transistor Output Optocouplers PHOTO TRANS")
      (fields (field (name "MF") "ON Semiconductor / Fairchild") (field (name "MP") "4N35SM"))
      (libsource (lib "4N35SM") (part "4N35SM"))
    )
    (comp (ref "X1")
      (value "Crystal")
      (footprint "ABRA-ABLS2-2_V")
      (fields (field (name "MANUFACTURER") "Abracon") (field (name "PARTNUMBER") "ABLS2-4.096MHZ-D4Y-T"))
      (libsource (lib "Altium Content Vault") (part "ABRA-XTAL_1-2-2"))
    )
  )
  (nets
    (net (code "1") (name "+3.3") (class "Default")
      (node (ref "C2") (pin "1") (pinfunction "1_1") (pintype "passive"))
      (node (ref "C29") (pin "1") (pinfunction "1_1") (pintype "passive"))
      (node (ref "C30") (pin "1") (pinfunction "1_1") (pintype "passive"))
      (node (ref "C6") (pin "2") (pinfunction "2_2") (pintype "passive"))
      (node (ref "C7") (pin "2") (pinfunction "2_2") (pintype "passive"))
      (node (ref "L1") (pin "2") (pinfunction "2_2") (pintype "passive"))
      (node (ref "L2") (pin "1") (pinfunction "1_1") (pintype "passive"))
      (node (ref "P1") (pin "1") (pinfunction "1_1") (pintype "passive"))
      (node (ref "P2") (pin "2") (pinfunction "2_2") (pintype "passive"))
      (node (ref "P2") (pin "3") (pinfunction "3_3") (pintype "passive"))
      (node (ref "R12") (pin "2") (pinfunction "2_2") (pintype "passive"))
      (node (ref "R16") (pin "2") (pinfunction "2_2") (pintype "passive"))
      (node (ref "R19") (pin "2") (pinfunction "2_2") (pintype "passive"))
      (node (ref "R25") (pin "2") (pinfunction "2_2") (pintype "passive"))
      (node (ref "R29") (pin "2") (pinfunction "2_2") (pintype "passive"))
      (node (ref "R3") (pin "2") (pinfunction "2_2") (pintype "passive"))
      (node (ref "U1") (pin "8") (pinfunction "VCC2_8") (pintype "power_in"))
      (node (ref "U2") (pin "1") (pinfunction "FB_1") (pintype "passive"))
    )
    (net (code "2") (name "+12") (class "Default")
      (node (ref "D13") (pin "1") (pinfunction "C_1") (pintype "passive"))
      (node (ref "D17") (pin "1") (pinfunction "C_1") (pintype "passive"))
      (node (ref "D19") (pin "1") (pinfunction "C_1") (pintype "passive"))
      (node (ref "D2") (pin "1") (pinfunction "C_1") (pintype "passive"))
      (node (ref "D21") (pin "1") (pinfunction "C_1") (pintype "passive"))
      (node (ref "D7") (pin "2") (pinfunction "K_2") (pintype "passive"))
      (node (ref "D9") (pin "1") (pinfunction "C_1") (pintype "passive"))
      (node (ref "K1") (pin "A1") (pinfunction "A1_A1") (pintype "passive"))
      (node (ref "K2") (pin "A1") (pinfunction "A1_A1") (pintype "passive"))
      (node (ref "K3") (pin "A1") (pinfunction "A1_A1") (pintype "passive"))
      (node (ref "K4") (pin "A1") (pinfunction "A1_A1") (pintype "passive"))
      (node (ref "K5") (pin "8") (pinfunction "8_8") (pintype "passive"))
      (node (ref "K6") (pin "8") (pinfunction "8_8") (pintype "passive"))
      (node (ref "R1") (pin "2") (pinfunction "2_2") (pintype "passive"))
      (node (ref "R10") (pin "2") (pinfunction "2_2") (pintype "passive"))
      (node (ref "R14") (pin "2") (pinfunction "2_2") (pintype "passive"))
      (node (ref "R15") (pin "2") (pinfunction "2_2") (pintype "passive"))
      (node (ref "R2") (pin "2") (pinfunction "2_2") (pintype "passive"))
      (node (ref "R6") (pin "2") (pinfunction "2_2") (pintype "passive"))
      (node (ref "R8") (pin "2") (pinfunction "2_2") (pintype "passive"))
      (node (ref "U2") (pin "2") (pinfunction "EN_2") (pintype "input"))
      (node (ref "U2") (pin "3") (pinfunction "VIN_3") (pintype "power_in"))
      (node (ref "U3") (pin "9") (pinfunction "COM_9") (pintype "passive"))
    )
    (net (code "3") (name "/GND1") (class "Default")
      (node (ref "C1") (pin "2") (pinfunction "2_2") (pintype "passive"))
      (node (ref "J1") (pin "A7") (pinfunction "A7_A7") (pintype "passive"))
      (node (ref "J1") (pin "C7") (pinfunction "C7_C7") (pintype "passive"))
      (node (ref "U1") (pin "4") (pinfunction "GND1_4") (pintype "power_in"))
    )
    (net (code "4") (name "/Interlock") (class "Default")
      (node (ref "J3") (pin "2") (pinfunction "2_2") (pintype "passive"))
      (node (ref "U4") (pin "12") (pinfunction "PA2_12") (pintype "bidirectional"))
    )
    (net (code "5") (name "/L1") (class "Default")
      (node (ref "J") (pin "5") (pinfunction "5_5") (pintype "passive"))
      (node (ref "J") (pin "6") (pinfunction "6_6") (pintype "passive"))
      (node (ref "K1") (pin "B2") (pinfunction "B2_B2") (pintype "passive"))
      (node (ref "R17") (pin "1") (pinfunction "1_1") (pintype "passive"))
    )
    (net (code "6") (name "/L1_out") (class "Default")
      (node (ref "J") (pin "7") (pinfunction "7_7") (pintype "passive"))
      (node (ref "J") (pin "8") (pinfunction "8_8") (pintype "passive"))
      (node (ref "K1") (pin "B1") (pinfunction "B1_B1") (pintype "passive"))
    )
    (net (code "7") (name "/L2") (class "Default")
      (node (ref "J4") (pin "7") (pinfunction "7_7") (pintype "passive"))
      (node (ref "J4") (pin "8") (pinfunction "8_8") (pintype "passive"))
      (node (ref "K3") (pin "B2") (pinfunction "B2_B2") (pintype "passive"))
      (node (ref "R23") (pin "1") (pinfunction "1_1") (pintype "passive"))
    )
    (net (code "8") (name "/L2_out") (class "Default")
      (node (ref "J4") (pin "5") (pinfunction "5_5") (pintype "passive"))
      (node (ref "J4") (pin "6") (pinfunction "6_6") (pintype "passive"))
      (node (ref "K3") (pin "B1") (pinfunction "B1_B1") (pintype "passive"))
    )
    (net (code "9") (name "/N1") (class "Default")
      (node (ref "J") (pin "10") (pinfunction "10_10") (pintype "passive"))
      (node (ref "J") (pin "9") (pinfunction "9_9") (pintype "passive"))
      (node (ref "K2") (pin "B2") (pinfunction "B2_B2") (pintype "passive"))
      (node (ref "R20") (pin "1") (pinfunction "1_1") (pintype "passive"))
    )
    (net (code "10") (name "/N1_out") (class "Default")
      (node (ref "J") (pin "11") (pinfunction "11_11") (pintype "passive"))
      (node (ref "J") (pin "12") (pinfunction "12_12") (pintype "passive"))
      (node (ref "K2") (pin "B1") (pinfunction "B1_B1") (pintype "passive"))
    )
    (net (code "11") (name "/N2") (class "Default")
      (node (ref "J4") (pin "3") (pinfunction "3_3") (pintype "passive"))
      (node (ref "J4") (pin "4") (pinfunction "4_4") (pintype "passive"))
      (node (ref "K4") (pin "B2") (pinfunction "B2_B2") (pintype "passive"))
      (node (ref "R26") (pin "1") (pinfunction "1_1") (pintype "passive"))
    )
    (net (code "12") (name "/N2_out") (class "Default")
      (node (ref "J4") (pin "1") (pinfunction "1_1") (pintype "passive"))
      (node (ref "J4") (pin "2") (pinfunction "2_2") (pintype "passive"))
      (node (ref "K4") (pin "B1") (pinfunction "B1_B1") (pintype "passive"))
    )
    (net (code "13") (name "/NRST") (class "Default")
      (node (ref "C11") (pin "1") (pinfunction "1_1") (pintype "passive"))
      (node (ref "P1") (pin "10") (pinfunction "10_10") (pintype "passive"))
      (node (ref "S2") (pin "1") (pinfunction "COM_1") (pintype "passive"))
      (node (ref "S2") (pin "2") (pinfunction "COM_2") (pintype "passive"))
      (node (ref "U4") (pin "7") (pinfunction "NRST_7") (pintype "bidirectional"))
    )
    (net (code "14") (name "/R1") (class "Default")
      (node (ref "U3") (pin "1") (pinfunction "1B_1") (pintype "input"))
      (node (ref "U4") (pin "45") (pinfunction "PB8_45") (pintype "bidirectional"))
    )
    (net (code "15") (name "/R2") (class "Default")
      (node (ref "U3") (pin "2") (pinfunction "2B_2") (pintype "input"))
      (node (ref "U4") (pin "46") (pinfunction "PB9_46") (pintype "bidirectional"))
    )
    (net (code "16") (name "/R3") (class "Default")
      (node (ref "U3") (pin "3") (pinfunction "3B_3") (pintype "input"))
      (node (ref "U4") (pin "21") (pinfunction "PB10_21") (pintype "bidirectional"))
    )
    (net (code "17") (name "/R4") (class "Default")
      (node (ref "U3") (pin "4") (pinfunction "4B_4") (pintype "input"))
      (node (ref "U4") (pin "22") (pinfunction "PB11_22") (pintype "bidirectional"))
    )
    (net (code "18") (name "/S1_COM") (class "Default")
      (node (ref "J2") (pin "5") (pinfunction "5_5") (pintype "passive"))
      (node (ref "J2") (pin "6") (pinfunction "6_6") (pintype "passive"))
      (node (ref "K5") (pin "3") (pinfunction "3_3") (pintype "passive"))
      (node (ref "K5") (pin "6") (pinfunction "6_6") (pintype "passive"))
    )
    (net (code "19") (name "/S1_NC") (class "Default")
      (node (ref "J2") (pin "1") (pinfunction "1_1") (pintype "passive"))
      (node (ref "J2") (pin "2") (pinfunction "2_2") (pintype "passive"))
      (node (ref "K5") (pin "2") (pinfunction "2_2") (pintype "passive"))
      (node (ref "K5") (pin "7") (pinfunction "7_7") (pintype "passive"))
    )
    (net (code "20") (name "/S1_NO") (class "Default")
      (node (ref "J2") (pin "3") (pinfunction "3_3") (pintype "passive"))
      (node (ref "J2") (pin "4") (pinfunction "4_4") (pintype "passive"))
      (node (ref "K5") (pin "4") (pinfunction "4_4") (pintype "passive"))
      (node (ref "K5") (pin "5") (pinfunction "5_5") (pintype "passive"))
    )
    (net (code "21") (name "/S2_COM") (class "Default")
      (node (ref "J2") (pin "11") (pinfunction "11_11") (pintype "passive"))
      (node (ref "J2") (pin "12") (pinfunction "12_12") (pintype "passive"))
      (node (ref "K6") (pin "3") (pinfunction "3_3") (pintype "passive"))
      (node (ref "K6") (pin "6") (pinfunction "6_6") (pintype "passive"))
    )
    (net (code "22") (name "/S2_NC") (class "Default")
      (node (ref "J2") (pin "7") (pinfunction "7_7") (pintype "passive"))
      (node (ref "J2") (pin "8") (pinfunction "8_8") (pintype "passive"))
      (node (ref "K6") (pin "2") (pinfunction "2_2") (pintype "passive"))
      (node (ref "K6") (pin "7") (pinfunction "7_7") (pintype "passive"))
    )
    (net (code "23") (name "/S2_NO") (class "Default")
      (node (ref "J2") (pin "10") (pinfunction "10_10") (pintype "passive"))
      (node (ref "J2") (pin "9") (pinfunction "9_9") (pintype "passive"))
      (node (ref "K6") (pin "4") (pinfunction "4_4") (pintype "passive"))
      (node (ref "K6") (pin "5") (pinfunction "5_5") (pintype "passive"))
    )
    (net (code "24") (name "/SCL") (class "Default")
      (node (ref "P2") (pin "6") (pinfunction "6_6") (pintype "passive"))
      (node (ref "R16") (pin "1") (pinfunction "1_1") (pintype "passive"))
      (node (ref "U1") (pin "6") (pinfunction "SCL2_6") (pintype "input"))
      (node (ref "U4") (pin "38") (pinfunction "PA15_38") (pintype "bidirectional"))
    )
    (net (code "25") (name "/SCL1") (class "Default")
      (node (ref "J1") (pin "A5") (pinfunction "A5_A5") (pintype "passive"))
      (node (ref "J1") (pin "C5") (pinfunction "C5_C5") (pintype "passive"))
      (node (ref "U1") (pin "3") (pinfunction "SCL1_3") (pintype "input"))
    )
    (net (code "26") (name "/SDA") (class "Default")
      (node (ref "P1") (pin "4") (pinfunction "4_4") (pintype "passive"))
      (node (ref "P2") (pin "4") (pinfunction "4_4") (pintype "passive"))
      (node (ref "R29") (pin "1") (pinfunction "1_1") (pintype "passive"))
      (node (ref "U1") (pin "7") (pinfunction "SDA2_7") (pintype "bidirectional"))
      (node (ref "U4") (pin "37") (pinfunction "PA14_37") (pintype "bidirectional"))
    )
    (net (code "27") (name "/SDA1") (class "Default")
      (node (ref "J1") (pin "A3") (pinfunction "A3_A3") (pintype "passive"))
      (node (ref "J1") (pin "C3") (pinfunction "C3_C3") (pintype "passive"))
      (node (ref "U1") (pin "2") (pinfunction "SDA1_2") (pintype "bidirectional"))
    )
    (net (code "28") (name "/START") (class "Default")
      (node (ref "C10") (pin "1") (pinfunction "1_1") (pintype "passive"))
      (node (ref "R12") (pin "1") (pinfunction "1_1") (pintype "passive"))
      (node (ref "S1") (pin "1") (pinfunction "COM_1") (pintype "passive"))
      (node (ref "S1") (pin "2") (pinfunction "COM_2") (pintype "passive"))
      (node (ref "U4") (pin "33") (pinfunction "PA12_33") (pintype "bidirectional"))
    )
    (net (code "29") (name "/SWDIO") (class "Default")
      (node (ref "P1") (pin "2") (pinfunction "2_2") (pintype "passive"))
      (node (ref "P2") (pin "5") (pinfunction "5_5") (pintype "passive"))
      (node (ref "U4") (pin "34") (pinfunction "PA13_34") (pintype "bidirectional"))
    )
    (net (code "30") (name "/VCC1") (class "Default")
      (node (ref "C1") (pin "1") (pinfunction "1_1") (pintype "passive"))
      (node (ref "J1") (pin "A1") (pinfunction "A1_A1") (pintype "passive"))
      (node (ref "J1") (pin "C1") (pinfunction "C1_C1") (pintype "passive"))
      (node (ref "U1") (pin "1") (pinfunction "VCC1_1") (pintype "power_in"))
    )
    (net (code "31") (name "/ZCD1") (class "Default")
      (node (ref "R19") (pin "1") (pinfunction "1_1") (pintype "passive"))
      (node (ref "U4") (pin "10") (pinfunction "PA0_10") (pintype "bidirectional"))
      (node (ref "U5") (pin "5") (pinfunction "CO_5") (pintype "passive"))
    )
    (net (code "32") (name "/ZCD2") (class "Default")
      (node (ref "R25") (pin "1") (pinfunction "1_1") (pintype "passive"))
      (node (ref "U4") (pin "11") (pinfunction "PA1_11") (pintype "bidirectional"))
      (node (ref "U6") (pin "5") (pinfunction "CO_5") (pintype "passive"))
    )
    (net (code "33") (name "AGND") (class "Default")
      (node (ref "C21") (pin "2") (pinfunction "2_2") (pintype "passive"))
      (node (ref "C22") (pin "2") (pinfunction "2_2") (pintype "passive"))
      (node (ref "C23") (pin "2") (pinfunction "2_2") (pintype "passive"))
      (node (ref "C24") (pin "1") (pinfunction "1_1") (pintype "passive"))
      (node (ref "C8") (pin "2") (pinfunction "2_2") (pintype "passive"))
      (node (ref "C9") (pin "2") (pinfunction "2_2") (pintype "passive"))
      (node (ref "D6") (pin "1") (pinfunction "C_1") (pintype "passive"))
      (node (ref "R7") (pin "2") (pinfunction "2_2") (pintype "passive"))
      (node (ref "U4") (pin "8") (pinfunction "VSSA/VREF-_8") (pintype "power_in"))
    )
    (net (code "34") (name "AVCC") (class "Default")
      (node (ref "C21") (pin "1") (pinfunction "1_1") (pintype "passive"))
      (node (ref "C22") (pin "1") (pinfunction "1_1") (pintype "passive"))
      (node (ref "C23") (pin "1") (pinfunction "1_1") (pintype "passive"))
      (node (ref "C24") (pin "2") (pinfunction "2_2") (pintype "passive"))
      (node (ref "C8") (pin "1") (pinfunction "1_1") (pintype "passive"))
      (node (ref "C9") (pin "1") (pinfunction "1_1") (pintype "passive"))
      (node (ref "L3") (pin "2") (pinfunction "2_2") (pintype "passive"))
      (node (ref "R5") (pin "2") (pinfunction "2_2") (pintype "passive"))
      (node (ref "U4") (pin "9") (pinfunction "VDDA/VREF+_9") (pintype "power_in"))
    )
    (net (code "35") (name "DVCC") (class "Default")
      (node (ref "C14") (pin "1") (pinfunction "1_1") (pintype "passive"))
      (node (ref "C15") (pin "1") (pinfunction "1_1") (pintype "passive"))
      (node (ref "C16") (pin "1") (pinfunction "1_1") (pintype "passive"))
      (node (ref "C17") (pin "1") (pinfunction "1_1") (pintype "passive"))
      (node (ref "C18") (pin "2") (pinfunction "2_2") (pintype "passive"))
      (node (ref "C19") (pin "1") (pinfunction "1_1") (pintype "passive"))
      (node (ref "C20") (pin "1") (pinfunction "1_1") (pintype "passive"))
      (node (ref "C4") (pin "1") (pinfunction "1_1") (pintype "passive"))
      (node (ref "C5") (pin "1") (pinfunction "1_1") (pintype "passive"))
      (node (ref "D11") (pin "1") (pinfunction "K_1") (pintype "passive"))
      (node (ref "L2") (pin "2") (pinfunction "2_2") (pintype "passive"))
      (node (ref "L3") (pin "1") (pinfunction "1_1") (pintype "passive"))
      (node (ref "R4") (pin "2") (pinfunction "2_2") (pintype "passive"))
      (node (ref "S") (pin "2") (pinfunction "2_2") (pintype "passive"))
      (node (ref "U4") (pin "1") (pinfunction "VBAT_1") (pintype "power_in"))
      (node (ref "U4") (pin "24") (pinfunction "VDD_24") (pintype "power_in"))
      (node (ref "U4") (pin "36") (pinfunction "VDD_36") (pintype "power_in"))
      (node (ref "U4") (pin "48") (pinfunction "VDD_48") (pintype "power_in"))
    )
    (net (code "36") (name "GND") (class "Default")
      (node (ref "C10") (pin "2") (pinfunction "2_2") (pintype "passive"))
      (node (ref "C11") (pin "2") (pinfunction "2_2") (pintype "passive"))
      (node (ref "C12") (pin "2") (pinfunction "2_2") (pintype "passive"))
      (node (ref "C13") (pin "2") (pinfunction "2_2") (pintype "passive"))
      (node (ref "C14") (pin "2") (pinfunction "2_2") (pintype "passive"))
      (node (ref "C15") (pin "2") (pinfunction "2_2") (pintype "passive"))
      (node (ref "C16") (pin "2") (pinfunction "2_2") (pintype "passive"))
      (node (ref "C17") (pin "2") (pinfunction "2_2") (pintype "passive"))
      (node (ref "C18") (pin "1") (pinfunction "1_1") (pintype "passive"))
      (node (ref "C19") (pin "2") (pinfunction "2_2") (pintype "passive"))
      (node (ref "C2") (pin "2") (pinfunction "2_2") (pintype "passive"))
      (node (ref "C20") (pin "2") (pinfunction "2_2") (pintype "passive"))
      (node (ref "C29") (pin "2") (pinfunction "2_2") (pintype "passive"))
      (node (ref "C30") (pin "2") (pinfunction "2_2") (pintype "passive"))
      (node (ref "C4") (pin "2") (pinfunction "2_2") (pintype "passive"))
      (node (ref "C5") (pin "2") (pinfunction "2_2") (pintype "passive"))
      (node (ref "C6") (pin "1") (pinfunction "1_1") (pintype "passive"))
      (node (ref "C7") (pin "1") (pinfunction "1_1") (pintype "passive"))
      (node (ref "D10") (pin "2") (pinfunction "2_2") (pintype "passive"))
      (node (ref "D11") (pin "2") (pinfunction "A_2") (pintype "passive"))
      (node (ref "D14") (pin "1") (pinfunction "C_1") (pintype "passive"))
      (node (ref "D15") (pin "1") (pinfunction "C_1") (pintype "passive"))
      (node (ref "D3") (pin "1") (pinfunction "C_1") (pintype "passive"))
      (node (ref "D4") (pin "1") (pinfunction "C_1") (pintype "passive"))
      (node (ref "D5") (pin "1") (pinfunction "C_1") (pintype "passive"))
      (node (ref "J1") (pin "A31") (pinfunction "A31_A31") (pintype "passive"))
      (node (ref "J1") (pin "C31") (pinfunction "C31_C31") (pintype "passive"))
      (node (ref "J3") (pin "1") (pinfunction "1_1") (pintype "passive"))
      (node (ref "P1") (pin "3") (pinfunction "3_3") (pintype "passive"))
      (node (ref "P1") (pin "5") (pinfunction "5_5") (pintype "passive"))
      (node (ref "P1") (pin "9") (pinfunction "9_9") (pintype "passive"))
      (node (ref "P2") (pin "1") (pinfunction "1_1") (pintype "passive"))
      (node (ref "R13") (pin "1") (pinfunction "1_1") (pintype "passive"))
      (node (ref "R7") (pin "1") (pinfunction "1_1") (pintype "passive"))
      (node (ref "S1") (pin "3") (pinfunction "NO_3") (pintype "passive"))
      (node (ref "S1") (pin "4") (pinfunction "NO_4") (pintype "passive"))
      (node (ref "S2") (pin "3") (pinfunction "NO_3") (pintype "passive"))
      (node (ref "S2") (pin "4") (pinfunction "NO_4") (pintype "passive"))
      (node (ref "U1") (pin "5") (pinfunction "GND2_5") (pintype "power_in"))
      (node (ref "U2") (pin "4") (pinfunction "GND_4") (pintype "power_in"))
      (node (ref "U3") (pin "8") (pinfunction "E_8") (pintype "passive"))
      (node (ref "U4") (pin "23") (pinfunction "VSS_23") (pintype "power_in"))
      (node (ref "U4") (pin "35") (pinfunction "VSS_35") (pintype "power_in"))
      (node (ref "U4") (pin "47") (pinfunction "VSS_47") (pintype "power_in"))
      (node (ref "U5") (pin "4") (pinfunction "E_4") (pintype "passive"))
      (node (ref "U6") (pin "4") (pinfunction "E_4") (pintype "passive"))
    )
    (net (code "37") (name "Net-(D1-A)") (class "Default")
      (node (ref "D1") (pin "2") (pinfunction "A_2") (pintype "passive"))
      (node (ref "R1") (pin "1") (pinfunction "1_1") (pintype "passive"))
    )
    (net (code "38") (name "Net-(D1-C)") (class "Default")
      (node (ref "D1") (pin "1") (pinfunction "C_1") (pintype "passive"))
      (node (ref "D2") (pin "2") (pinfunction "A_2") (pintype "passive"))
      (node (ref "D8") (pin "1") (pinfunction "C_1") (pintype "passive"))
      (node (ref "D9") (pin "2") (pinfunction "A_2") (pintype "passive"))
      (node (ref "K1") (pin "A2") (pinfunction "A2_A2") (pintype "passive"))
      (node (ref "K2") (pin "A2") (pinfunction "A2_A2") (pintype "passive"))
      (node (ref "U3") (pin "16") (pinfunction "1C_16") (pintype "output"))
    )
    (net (code "39") (name "Net-(D3-A)") (class "Default")
      (node (ref "D3") (pin "2") (pinfunction "A_2") (pintype "passive"))
      (node (ref "R2") (pin "1") (pinfunction "1_1") (pintype "passive"))
    )
    (net (code "40") (name "Net-(D4-A)") (class "Default")
      (node (ref "D4") (pin "2") (pinfunction "A_2") (pintype "passive"))
      (node (ref "R3") (pin "1") (pinfunction "1_1") (pintype "passive"))
    )
    (net (code "41") (name "Net-(D5-A)") (class "Default")
      (node (ref "D5") (pin "2") (pinfunction "A_2") (pintype "passive"))
      (node (ref "R4") (pin "1") (pinfunction "1_1") (pintype "passive"))
    )
    (net (code "42") (name "Net-(D6-A)") (class "Default")
      (node (ref "D6") (pin "2") (pinfunction "A_2") (pintype "passive"))
      (node (ref "R5") (pin "1") (pinfunction "1_1") (pintype "passive"))
    )
    (net (code "43") (name "Net-(D7-A)") (class "Default")
      (node (ref "D7") (pin "1") (pinfunction "A_1") (pintype "passive"))
      (node (ref "F1") (pin "2") (pinfunction "2_2") (pintype "passive"))
    )
    (net (code "44") (name "Net-(D8-A)") (class "Default")
      (node (ref "D8") (pin "2") (pinfunction "A_2") (pintype "passive"))
      (node (ref "R6") (pin "1") (pinfunction "1_1") (pintype "passive"))
    )
    (net (code "45") (name "Net-(D12-A)") (class "Default")
      (node (ref "D12") (pin "2") (pinfunction "A_2") (pintype "passive"))
      (node (ref "R8") (pin "1") (pinfunction "1_1") (pintype "passive"))
    )
    (net (code "46") (name "Net-(D12-C)") (class "Default")
      (node (ref "D12") (pin "1") (pinfunction "C_1") (pintype "passive"))
      (node (ref "D13") (pin "2") (pinfunction "A_2") (pintype "passive"))
      (node (ref "D16") (pin "1") (pinfunction "C_1") (pintype "passive"))
      (node (ref "D17") (pin "2") (pinfunction "A_2") (pintype "passive"))
      (node (ref "K3") (pin "A2") (pinfunction "A2_A2") (pintype "passive"))
      (node (ref "K4") (pin "A2") (pinfunction "A2_A2") (pintype "passive"))
      (node (ref "U3") (pin "15") (pinfunction "2C_15") (pintype "output"))
    )
    (net (code "47") (name "Net-(D14-A)") (class "Default")
      (node (ref "D14") (pin "2") (pinfunction "A_2") (pintype "passive"))
      (node (ref "R9") (pin "1") (pinfunction "1_1") (pintype "passive"))
    )
    (net (code "48") (name "Net-(D15-A)") (class "Default")
      (node (ref "D15") (pin "2") (pinfunction "A_2") (pintype "passive"))
      (node (ref "R11") (pin "1") (pinfunction "1_1") (pintype "passive"))
    )
    (net (code "49") (name "Net-(D16-A)") (class "Default")
      (node (ref "D16") (pin "2") (pinfunction "A_2") (pintype "passive"))
      (node (ref "R10") (pin "1") (pinfunction "1_1") (pintype "passive"))
    )
    (net (code "50") (name "Net-(D18-A)") (class "Default")
      (node (ref "D18") (pin "2") (pinfunction "A_2") (pintype "passive"))
      (node (ref "R14") (pin "1") (pinfunction "1_1") (pintype "passive"))
    )
    (net (code "51") (name "Net-(D18-C)") (class "Default")
      (node (ref "D18") (pin "1") (pinfunction "C_1") (pintype "passive"))
      (node (ref "D19") (pin "2") (pinfunction "A_2") (pintype "passive"))
      (node (ref "K5") (pin "1") (pinfunction "1_1") (pintype "passive"))
      (node (ref "U3") (pin "14") (pinfunction "3C_14") (pintype "output"))
    )
    (net (code "52") (name "Net-(D20-A)") (class "Default")
      (node (ref "D20") (pin "2") (pinfunction "A_2") (pintype "passive"))
      (node (ref "R15") (pin "1") (pinfunction "1_1") (pintype "passive"))
    )
    (net (code "53") (name "Net-(D20-C)") (class "Default")
      (node (ref "D20") (pin "1") (pinfunction "C_1") (pintype "passive"))
      (node (ref "D21") (pin "2") (pinfunction "A_2") (pintype "passive"))
      (node (ref "K6") (pin "1") (pinfunction "1_1") (pintype "passive"))
      (node (ref "U3") (pin "13") (pinfunction "4C_13") (pintype "output"))
    )
    (net (code "54") (name "Net-(D24-A)") (class "Default")
      (node (ref "C26") (pin "1") (pinfunction "1_1") (pintype "passive"))
      (node (ref "D24") (pin "1") (pinfunction "A_1") (pintype "passive"))
      (node (ref "D28") (pin "2") (pinfunction "K_2") (pintype "passive"))
      (node (ref "R17") (pin "2") (pinfunction "2_2") (pintype "passive"))
    )
    (net (code "55") (name "Net-(D24-K)") (class "Default")
      (node (ref "C25") (pin "2") (pinfunction "2_2") (pintype "passive"))
      (node (ref "D24") (pin "2") (pinfunction "K_2") (pintype "passive"))
      (node (ref "D25") (pin "2") (pinfunction "K_2") (pintype "passive"))
      (node (ref "R18") (pin "1") (pinfunction "1_1") (pintype "passive"))
      (node (ref "R21") (pin "2") (pinfunction "2_2") (pintype "passive"))
    )
    (net (code "56") (name "Net-(D25-A)") (class "Default")
      (node (ref "C26") (pin "2") (pinfunction "2_2") (pintype "passive"))
      (node (ref "D25") (pin "1") (pinfunction "A_1") (pintype "passive"))
      (node (ref "D26") (pin "2") (pinfunction "K_2") (pintype "passive"))
      (node (ref "R20") (pin "2") (pinfunction "2_2") (pintype "passive"))
    )
    (net (code "57") (name "Net-(D26-A)") (class "Default")
      (node (ref "D26") (pin "1") (pinfunction "A_1") (pintype "passive"))
      (node (ref "D27") (pin "2") (pinfunction "K_2") (pintype "passive"))
      (node (ref "D28") (pin "1") (pinfunction "A_1") (pintype "passive"))
      (node (ref "Q1") (pin "1") (pinfunction "B_1") (pintype "passive"))
      (node (ref "R21") (pin "1") (pinfunction "1_1") (pintype "passive"))
    )
    (net (code "58") (name "Net-(D27-A)") (class "Default")
      (node (ref "C25") (pin "1") (pinfunction "1_1") (pintype "passive"))
      (node (ref "D27") (pin "1") (pinfunction "A_1") (pintype "passive"))
      (node (ref "Q1") (pin "2") (pinfunction "E_2") (pintype "passive"))
    )
    (net (code "59") (name "Net-(D31-A)") (class "Default")
      (node (ref "C28") (pin "1") (pinfunction "1_1") (pintype "passive"))
      (node (ref "D31") (pin "1") (pinfunction "A_1") (pintype "passive"))
      (node (ref "D37") (pin "2") (pinfunction "K_2") (pintype "passive"))
      (node (ref "R23") (pin "2") (pinfunction "2_2") (pintype "passive"))
    )
    (net (code "60") (name "Net-(D31-K)") (class "Default")
      (node (ref "C27") (pin "2") (pinfunction "2_2") (pintype "passive"))
      (node (ref "D31") (pin "2") (pinfunction "K_2") (pintype "passive"))
      (node (ref "D32") (pin "2") (pinfunction "K_2") (pintype "passive"))
      (node (ref "R24") (pin "1") (pinfunction "1_1") (pintype "passive"))
      (node (ref "R27") (pin "2") (pinfunction "2_2") (pintype "passive"))
    )
    (net (code "61") (name "Net-(D32-A)") (class "Default")
      (node (ref "C28") (pin "2") (pinfunction "2_2") (pintype "passive"))
      (node (ref "D32") (pin "1") (pinfunction "A_1") (pintype "passive"))
      (node (ref "D33") (pin "2") (pinfunction "K_2") (pintype "passive"))
      (node (ref "R26") (pin "2") (pinfunction "2_2") (pintype "passive"))
    )
    (net (code "62") (name "Net-(D33-A)") (class "Default")
      (node (ref "D33") (pin "1") (pinfunction "A_1") (pintype "passive"))
      (node (ref "D34") (pin "2") (pinfunction "K_2") (pintype "passive"))
      (node (ref "D37") (pin "1") (pinfunction "A_1") (pintype "passive"))
      (node (ref "Q2") (pin "1") (pinfunction "B_1") (pintype "passive"))
      (node (ref "R27") (pin "1") (pinfunction "1_1") (pintype "passive"))
    )
    (net (code "63") (name "Net-(D34-A)") (class "Default")
      (node (ref "C27") (pin "1") (pinfunction "1_1") (pintype "passive"))
      (node (ref "D34") (pin "1") (pinfunction "A_1") (pintype "passive"))
      (node (ref "Q2") (pin "2") (pinfunction "E_2") (pintype "passive"))
    )
    (net (code "64") (name "Net-(J-Pad1)") (class "Default")
      (node (ref "J") (pin "1") (pinfunction "1_1") (pintype "passive"))
      (node (ref "J") (pin "2") (pinfunction "2_2") (pintype "passive"))
    )
    (net (code "65") (name "Net-(J-Pad3)") (class "Default")
      (node (ref "J") (pin "3") (pinfunction "3_3") (pintype "passive"))
      (node (ref "J") (pin "4") (pinfunction "4_4") (pintype "passive"))
    )
    (net (code "66") (name "Net-(J4-Pad10)") (class "Default")
      (node (ref "J4") (pin "10") (pinfunction "10_10") (pintype "passive"))
      (node (ref "J4") (pin "9") (pinfunction "9_9") (pintype "passive"))
    )
    (net (code "67") (name "Net-(J4-Pad11)") (class "Default")
      (node (ref "J4") (pin "11") (pinfunction "11_11") (pintype "passive"))
      (node (ref "J4") (pin "12") (pinfunction "12_12") (pintype "passive"))
    )
    (net (code "68") (name "Net-(Q1-C)") (class "Default")
      (node (ref "Q1") (pin "3") (pinfunction "C_3") (pintype "passive"))
      (node (ref "U5") (pin "2") (pinfunction "C_2") (pintype "passive"))
    )
    (net (code "69") (name "Net-(Q2-C)") (class "Default")
      (node (ref "Q2") (pin "3") (pinfunction "C_3") (pintype "passive"))
      (node (ref "U6") (pin "2") (pinfunction "C_2") (pintype "passive"))
    )
    (net (code "70") (name "Net-(U2-BST)") (class "Default")
      (node (ref "C3") (pin "1") (pinfunction "1_1") (pintype "passive"))
      (node (ref "U2") (pin "6") (pinfunction "BST_6") (pintype "passive"))
    )
    (net (code "71") (name "Net-(U2-SW)") (class "Default")
      (node (ref "C3") (pin "2") (pinfunction "2_2") (pintype "passive"))
      (node (ref "L1") (pin "1") (pinfunction "1_1") (pintype "passive"))
      (node (ref "U2") (pin "5") (pinfunction "SW_5") (pintype "passive"))
    )
    (net (code "72") (name "Net-(U4-BOOT0)") (class "Default")
      (node (ref "R13") (pin "2") (pinfunction "2_2") (pintype "passive"))
      (node (ref "S") (pin "1") (pinfunction "1_1") (pintype "passive"))
      (node (ref "U4") (pin "44") (pinfunction "BOOT0_44") (pintype "input"))
    )
    (net (code "73") (name "Net-(U4-PB6)") (class "Default")
      (node (ref "R9") (pin "2") (pinfunction "2_2") (pintype "passive"))
      (node (ref "U4") (pin "42") (pinfunction "PB6_42") (pintype "bidirectional"))
    )
    (net (code "74") (name "Net-(U4-PB7)") (class "Default")
      (node (ref "R11") (pin "2") (pinfunction "2_2") (pintype "passive"))
      (node (ref "U4") (pin "43") (pinfunction "PB7_43") (pintype "bidirectional"))
    )
    (net (code "75") (name "Net-(U4-PF0{slash}OSC_IN)") (class "Default")
      (node (ref "C13") (pin "1") (pinfunction "1_1") (pintype "passive"))
      (node (ref "U4") (pin "5") (pinfunction "PF0/OSC_IN_5") (pintype "bidirectional"))
      (node (ref "X1") (pin "1") (pinfunction "X1_1") (pintype "passive"))
    )
    (net (code "76") (name "Net-(U4-PF1{slash}OSC_OUT)") (class "Default")
      (node (ref "C12") (pin "1") (pinfunction "1_1") (pintype "passive"))
      (node (ref "U4") (pin "6") (pinfunction "PF1/OSC_OUT_6") (pintype "bidirectional"))
      (node (ref "X1") (pin "2") (pinfunction "X2_2") (pintype "passive"))
    )
    (net (code "77") (name "Net-(U5-A)") (class "Default")
      (node (ref "R18") (pin "2") (pinfunction "2_2") (pintype "passive"))
      (node (ref "U5") (pin "1") (pinfunction "A_1") (pintype "passive"))
    )
    (net (code "78") (name "Net-(U6-A)") (class "Default")
      (node (ref "R24") (pin "2") (pinfunction "2_2") (pintype "passive"))
      (node (ref "U6") (pin "1") (pinfunction "A_1") (pintype "passive"))
    )
    (net (code "79") (name "VCC") (class "Default")
      (node (ref "D10") (pin "1") (pinfunction "1_1") (pintype "passive"))
      (node (ref "F1") (pin "1") (pinfunction "1_1") (pintype "passive"))
      (node (ref "J1") (pin "A29") (pinfunction "A29_A29") (pintype "passive"))
      (node (ref "J1") (pin "C29") (pinfunction "C29_C29") (pintype "passive"))
    )
    (net (code "80") (name "unconnected-(J1-PadA2)") (class "Default")
      (node (ref "J1") (pin "A2") (pinfunction "A2_A2") (pintype "passive"))
    )
    (net (code "81") (name "unconnected-(J1-PadA4)") (class "Default")
      (node (ref "J1") (pin "A4") (pinfunction "A4_A4") (pintype "passive"))
    )
    (net (code "82") (name "unconnected-(J1-PadA6)") (class "Default")
      (node (ref "J1") (pin "A6") (pinfunction "A6_A6") (pintype "passive"))
    )
    (net (code "83") (name "unconnected-(J1-PadA8)") (class "Default")
      (node (ref "J1") (pin "A8") (pinfunction "A8_A8") (pintype "passive"))
    )
    (net (code "84") (name "unconnected-(J1-PadA9)") (class "Default")
      (node (ref "J1") (pin "A9") (pinfunction "A9_A9") (pintype "passive"))
    )
    (net (code "85") (name "unconnected-(J1-PadA10)") (class "Default")
      (node (ref "J1") (pin "A10") (pinfunction "A10_A10") (pintype "passive"))
    )
    (net (code "86") (name "unconnected-(J1-PadA11)") (class "Default")
      (node (ref "J1") (pin "A11") (pinfunction "A11_A11") (pintype "passive"))
    )
    (net (code "87") (name "unconnected-(J1-PadA12)") (class "Default")
      (node (ref "J1") (pin "A12") (pinfunction "A12_A12") (pintype "passive"))
    )
    (net (code "88") (name "unconnected-(J1-PadA13)") (class "Default")
      (node (ref "J1") (pin "A13") (pinfunction "A13_A13") (pintype "passive"))
    )
    (net (code "89") (name "unconnected-(J1-PadA14)") (class "Default")
      (node (ref "J1") (pin "A14") (pinfunction "A14_A14") (pintype "passive"))
    )
    (net (code "90") (name "unconnected-(J1-PadA15)") (class "Default")
      (node (ref "J1") (pin "A15") (pinfunction "A15_A15") (pintype "passive"))
    )
    (net (code "91") (name "unconnected-(J1-PadA16)") (class "Default")
      (node (ref "J1") (pin "A16") (pinfunction "A16_A16") (pintype "passive"))
    )
    (net (code "92") (name "unconnected-(J1-PadA17)") (class "Default")
      (node (ref "J1") (pin "A17") (pinfunction "A17_A17") (pintype "passive"))
    )
    (net (code "93") (name "unconnected-(J1-PadA18)") (class "Default")
      (node (ref "J1") (pin "A18") (pinfunction "A18_A18") (pintype "passive"))
    )
    (net (code "94") (name "unconnected-(J1-PadA19)") (class "Default")
      (node (ref "J1") (pin "A19") (pinfunction "A19_A19") (pintype "passive"))
    )
    (net (code "95") (name "unconnected-(J1-PadA20)") (class "Default")
      (node (ref "J1") (pin "A20") (pinfunction "A20_A20") (pintype "passive"))
    )
    (net (code "96") (name "unconnected-(J1-PadA21)") (class "Default")
      (node (ref "J1") (pin "A21") (pinfunction "A21_A21") (pintype "passive"))
    )
    (net (code "97") (name "unconnected-(J1-PadA22)") (class "Default")
      (node (ref "J1") (pin "A22") (pinfunction "A22_A22") (pintype "passive"))
    )
    (net (code "98") (name "unconnected-(J1-PadA23)") (class "Default")
      (node (ref "J1") (pin "A23") (pinfunction "A23_A23") (pintype "passive"))
    )
    (net (code "99") (name "unconnected-(J1-PadA24)") (class "Default")
      (node (ref "J1") (pin "A24") (pinfunction "A24_A24") (pintype "passive"))
    )
    (net (code "100") (name "unconnected-(J1-PadA25)") (class "Default")
      (node (ref "J1") (pin "A25") (pinfunction "A25_A25") (pintype "passive"))
    )
    (net (code "101") (name "unconnected-(J1-PadA26)") (class "Default")
      (node (ref "J1") (pin "A26") (pinfunction "A26_A26") (pintype "passive"))
    )
    (net (code "102") (name "unconnected-(J1-PadA27)") (class "Default")
      (node (ref "J1") (pin "A27") (pinfunction "A27_A27") (pintype "passive"))
    )
    (net (code "103") (name "unconnected-(J1-PadA28)") (class "Default")
      (node (ref "J1") (pin "A28") (pinfunction "A28_A28") (pintype "passive"))
    )
    (net (code "104") (name "unconnected-(J1-PadA30)") (class "Default")
      (node (ref "J1") (pin "A30") (pinfunction "A30_A30") (pintype "passive"))
    )
    (net (code "105") (name "unconnected-(J1-PadA32)") (class "Default")
      (node (ref "J1") (pin "A32") (pinfunction "A32_A32") (pintype "passive"))
    )
    (net (code "106") (name "unconnected-(J1-PadC2)") (class "Default")
      (node (ref "J1") (pin "C2") (pinfunction "C2_C2") (pintype "passive"))
    )
    (net (code "107") (name "unconnected-(J1-PadC4)") (class "Default")
      (node (ref "J1") (pin "C4") (pinfunction "C4_C4") (pintype "passive"))
    )
    (net (code "108") (name "unconnected-(J1-PadC6)") (class "Default")
      (node (ref "J1") (pin "C6") (pinfunction "C6_C6") (pintype "passive"))
    )
    (net (code "109") (name "unconnected-(J1-PadC8)") (class "Default")
      (node (ref "J1") (pin "C8") (pinfunction "C8_C8") (pintype "passive"))
    )
    (net (code "110") (name "unconnected-(J1-PadC9)") (class "Default")
      (node (ref "J1") (pin "C9") (pinfunction "C9_C9") (pintype "passive"))
    )
    (net (code "111") (name "unconnected-(J1-PadC10)") (class "Default")
      (node (ref "J1") (pin "C10") (pinfunction "C10_C10") (pintype "passive"))
    )
    (net (code "112") (name "unconnected-(J1-PadC11)") (class "Default")
      (node (ref "J1") (pin "C11") (pinfunction "C11_C11") (pintype "passive"))
    )
    (net (code "113") (name "unconnected-(J1-PadC12)") (class "Default")
      (node (ref "J1") (pin "C12") (pinfunction "C12_C12") (pintype "passive"))
    )
    (net (code "114") (name "unconnected-(J1-PadC13)") (class "Default")
      (node (ref "J1") (pin "C13") (pinfunction "C13_C13") (pintype "passive"))
    )
    (net (code "115") (name "unconnected-(J1-PadC14)") (class "Default")
      (node (ref "J1") (pin "C14") (pinfunction "C14_C14") (pintype "passive"))
    )
    (net (code "116") (name "unconnected-(J1-PadC15)") (class "Default")
      (node (ref "J1") (pin "C15") (pinfunction "C15_C15") (pintype "passive"))
    )
    (net (code "117") (name "unconnected-(J1-PadC16)") (class "Default")
      (node (ref "J1") (pin "C16") (pinfunction "C16_C16") (pintype "passive"))
    )
    (net (code "118") (name "unconnected-(J1-PadC17)") (class "Default")
      (node (ref "J1") (pin "C17") (pinfunction "C17_C17") (pintype "passive"))
    )
    (net (code "119") (name "unconnected-(J1-PadC18)") (class "Default")
      (node (ref "J1") (pin "C18") (pinfunction "C18_C18") (pintype "passive"))
    )
    (net (code "120") (name "unconnected-(J1-PadC19)") (class "Default")
      (node (ref "J1") (pin "C19") (pinfunction "C19_C19") (pintype "passive"))
    )
    (net (code "121") (name "unconnected-(J1-PadC20)") (class "Default")
      (node (ref "J1") (pin "C20") (pinfunction "C20_C20") (pintype "passive"))
    )
    (net (code "122") (name "unconnected-(J1-PadC21)") (class "Default")
      (node (ref "J1") (pin "C21") (pinfunction "C21_C21") (pintype "passive"))
    )
    (net (code "123") (name "unconnected-(J1-PadC22)") (class "Default")
      (node (ref "J1") (pin "C22") (pinfunction "C22_C22") (pintype "passive"))
    )
    (net (code "124") (name "unconnected-(J1-PadC23)") (class "Default")
      (node (ref "J1") (pin "C23") (pinfunction "C23_C23") (pintype "passive"))
    )
    (net (code "125") (name "unconnected-(J1-PadC24)") (class "Default")
      (node (ref "J1") (pin "C24") (pinfunction "C24_C24") (pintype "passive"))
    )
    (net (code "126") (name "unconnected-(J1-PadC25)") (class "Default")
      (node (ref "J1") (pin "C25") (pinfunction "C25_C25") (pintype "passive"))
    )
    (net (code "127") (name "unconnected-(J1-PadC26)") (class "Default")
      (node (ref "J1") (pin "C26") (pinfunction "C26_C26") (pintype "passive"))
    )
    (net (code "128") (name "unconnected-(J1-PadC27)") (class "Default")
      (node (ref "J1") (pin "C27") (pinfunction "C27_C27") (pintype "passive"))
    )
    (net (code "129") (name "unconnected-(J1-PadC28)") (class "Default")
      (node (ref "J1") (pin "C28") (pinfunction "C28_C28") (pintype "passive"))
    )
    (net (code "130") (name "unconnected-(J1-PadC30)") (class "Default")
      (node (ref "J1") (pin "C30") (pinfunction "C30_C30") (pintype "passive"))
    )
    (net (code "131") (name "unconnected-(J1-PadC32)") (class "Default")
      (node (ref "J1") (pin "C32") (pinfunction "C32_C32") (pintype "passive"))
    )
    (net (code "132") (name "unconnected-(J1-PadMH1)") (class "Default")
      (node (ref "J1") (pin "MH1") (pinfunction "MH1_MH1") (pintype "passive"))
    )
    (net (code "133") (name "unconnected-(J1-PadMH2)") (class "Default")
      (node (ref "J1") (pin "MH2") (pinfunction "MH2_MH2") (pintype "passive"))
    )
    (net (code "134") (name "unconnected-(P1-Pad6)") (class "Default")
      (node (ref "P1") (pin "6") (pinfunction "6_6") (pintype "passive+no_connect"))
    )
    (net (code "135") (name "unconnected-(P1-Pad7)") (class "Default")
      (node (ref "P1") (pin "7") (pinfunction "7_7") (pintype "passive+no_connect"))
    )
    (net (code "136") (name "unconnected-(P1-Pad8)") (class "Default")
      (node (ref "P1") (pin "8") (pinfunction "8_8") (pintype "passive+no_connect"))
    )
    (net (code "137") (name "unconnected-(S-Pad3)") (class "Default")
      (node (ref "S") (pin "3") (pinfunction "3_3") (pintype "passive"))
    )
    (net (code "138") (name "unconnected-(U3-5B-Pad5)") (class "Default")
      (node (ref "U3") (pin "5") (pinfunction "5B_5") (pintype "input+no_connect"))
    )
    (net (code "139") (name "unconnected-(U3-5C-Pad12)") (class "Default")
      (node (ref "U3") (pin "12") (pinfunction "5C_12") (pintype "output"))
    )
    (net (code "140") (name "unconnected-(U3-6B-Pad6)") (class "Default")
      (node (ref "U3") (pin "6") (pinfunction "6B_6") (pintype "input+no_connect"))
    )
    (net (code "141") (name "unconnected-(U3-6C-Pad11)") (class "Default")
      (node (ref "U3") (pin "11") (pinfunction "6C_11") (pintype "output"))
    )
    (net (code "142") (name "unconnected-(U3-7B-Pad7)") (class "Default")
      (node (ref "U3") (pin "7") (pinfunction "7B_7") (pintype "input+no_connect"))
    )
    (net (code "143") (name "unconnected-(U3-7C-Pad10)") (class "Default")
      (node (ref "U3") (pin "10") (pinfunction "7C_10") (pintype "output"))
    )
    (net (code "144") (name "unconnected-(U4-PA3-Pad13)") (class "Default")
      (node (ref "U4") (pin "13") (pinfunction "PA3_13") (pintype "bidirectional"))
    )
    (net (code "145") (name "unconnected-(U4-PA4-Pad14)") (class "Default")
      (node (ref "U4") (pin "14") (pinfunction "PA4_14") (pintype "bidirectional"))
    )
    (net (code "146") (name "unconnected-(U4-PA5-Pad15)") (class "Default")
      (node (ref "U4") (pin "15") (pinfunction "PA5_15") (pintype "bidirectional"))
    )
    (net (code "147") (name "unconnected-(U4-PA6-Pad16)") (class "Default")
      (node (ref "U4") (pin "16") (pinfunction "PA6_16") (pintype "bidirectional"))
    )
    (net (code "148") (name "unconnected-(U4-PA7-Pad17)") (class "Default")
      (node (ref "U4") (pin "17") (pinfunction "PA7_17") (pintype "bidirectional"))
    )
    (net (code "149") (name "unconnected-(U4-PA8-Pad29)") (class "Default")
      (node (ref "U4") (pin "29") (pinfunction "PA8_29") (pintype "bidirectional"))
    )
    (net (code "150") (name "unconnected-(U4-PA9-Pad30)") (class "Default")
      (node (ref "U4") (pin "30") (pinfunction "PA9_30") (pintype "bidirectional"))
    )
    (net (code "151") (name "unconnected-(U4-PA10-Pad31)") (class "Default")
      (node (ref "U4") (pin "31") (pinfunction "PA10_31") (pintype "bidirectional"))
    )
    (net (code "152") (name "unconnected-(U4-PA11-Pad32)") (class "Default")
      (node (ref "U4") (pin "32") (pinfunction "PA11_32") (pintype "bidirectional"))
    )
    (net (code "153") (name "unconnected-(U4-PB0-Pad18)") (class "Default")
      (node (ref "U4") (pin "18") (pinfunction "PB0_18") (pintype "bidirectional"))
    )
    (net (code "154") (name "unconnected-(U4-PB1-Pad19)") (class "Default")
      (node (ref "U4") (pin "19") (pinfunction "PB1_19") (pintype "bidirectional"))
    )
    (net (code "155") (name "unconnected-(U4-PB2-Pad20)") (class "Default")
      (node (ref "U4") (pin "20") (pinfunction "PB2_20") (pintype "bidirectional"))
    )
    (net (code "156") (name "unconnected-(U4-PB3-Pad39)") (class "Default")
      (node (ref "U4") (pin "39") (pinfunction "PB3_39") (pintype "bidirectional"))
    )
    (net (code "157") (name "unconnected-(U4-PB4-Pad40)") (class "Default")
      (node (ref "U4") (pin "40") (pinfunction "PB4_40") (pintype "bidirectional"))
    )
    (net (code "158") (name "unconnected-(U4-PB5-Pad41)") (class "Default")
      (node (ref "U4") (pin "41") (pinfunction "PB5_41") (pintype "bidirectional"))
    )
    (net (code "159") (name "unconnected-(U4-PB12-Pad25)") (class "Default")
      (node (ref "U4") (pin "25") (pinfunction "PB12_25") (pintype "bidirectional"))
    )
    (net (code "160") (name "unconnected-(U4-PB13-Pad26)") (class "Default")
      (node (ref "U4") (pin "26") (pinfunction "PB13_26") (pintype "bidirectional"))
    )
    (net (code "161") (name "unconnected-(U4-PB14-Pad27)") (class "Default")
      (node (ref "U4") (pin "27") (pinfunction "PB14_27") (pintype "bidirectional"))
    )
    (net (code "162") (name "unconnected-(U4-PB15-Pad28)") (class "Default")
      (node (ref "U4") (pin "28") (pinfunction "PB15_28") (pintype "bidirectional"))
    )
    (net (code "163") (name "unconnected-(U4-PC13-Pad2)") (class "Default")
      (node (ref "U4") (pin "2") (pinfunction "PC13_2") (pintype "bidirectional"))
    )
    (net (code "164") (name "unconnected-(U4-PC14{slash}OSC32_IN-Pad3)") (class "Default")
      (node (ref "U4") (pin "3") (pinfunction "PC14/OSC32_IN_3") (pintype "bidirectional"))
    )
    (net (code "165") (name "unconnected-(U4-PC15{slash}OSC32_OUT-Pad4)") (class "Default")
      (node (ref "U4") (pin "4") (pinfunction "PC15/OSC32_OUT_4") (pintype "bidirectional"))
    )
    (net (code "166") (name "unconnected-(U5-B-Pad6)") (class "Default")
      (node (ref "U5") (pin "6") (pinfunction "B_6") (pintype "passive"))
    )
    (net (code "167") (name "unconnected-(U6-B-Pad6)") (class "Default")
      (node (ref "U6") (pin "6") (pinfunction "B_6") (pintype "passive"))
    )
  )
)
